# controller.net
KiCad netlist of a schematic drawn in EAGLE
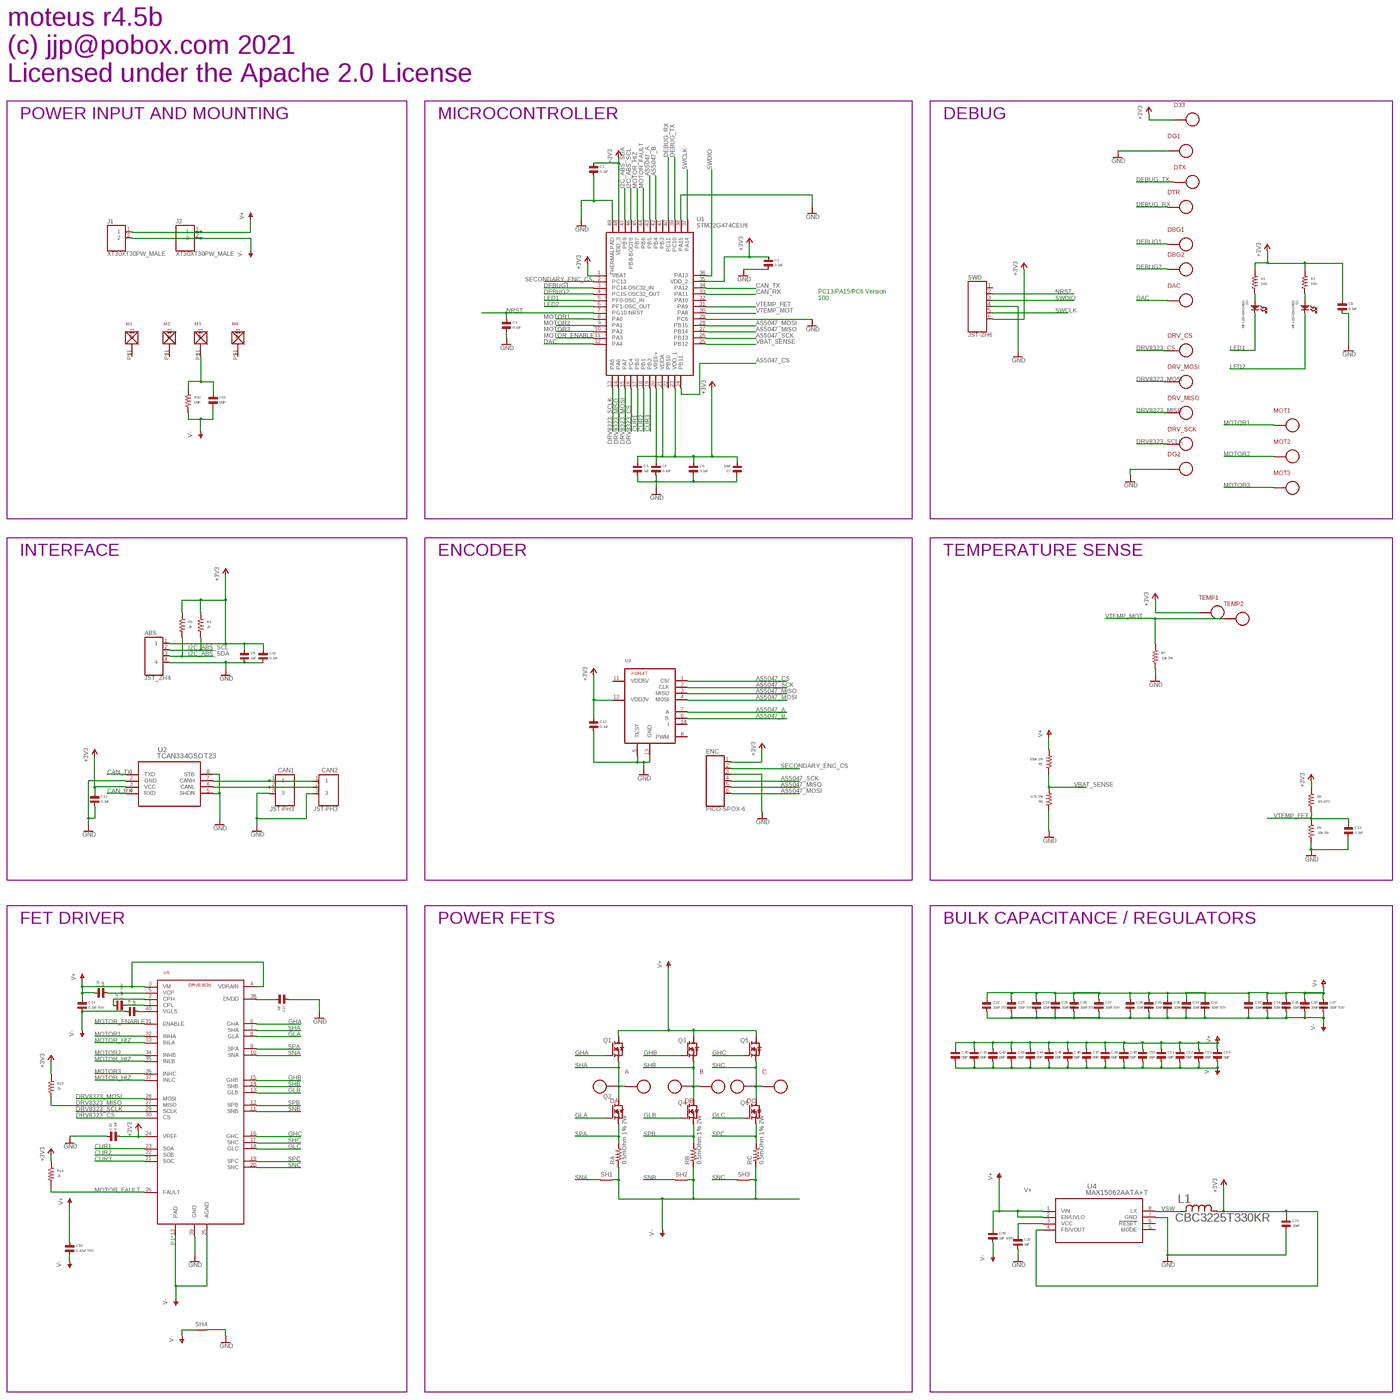
[diagram p0: schematic, sheet 1, overview]
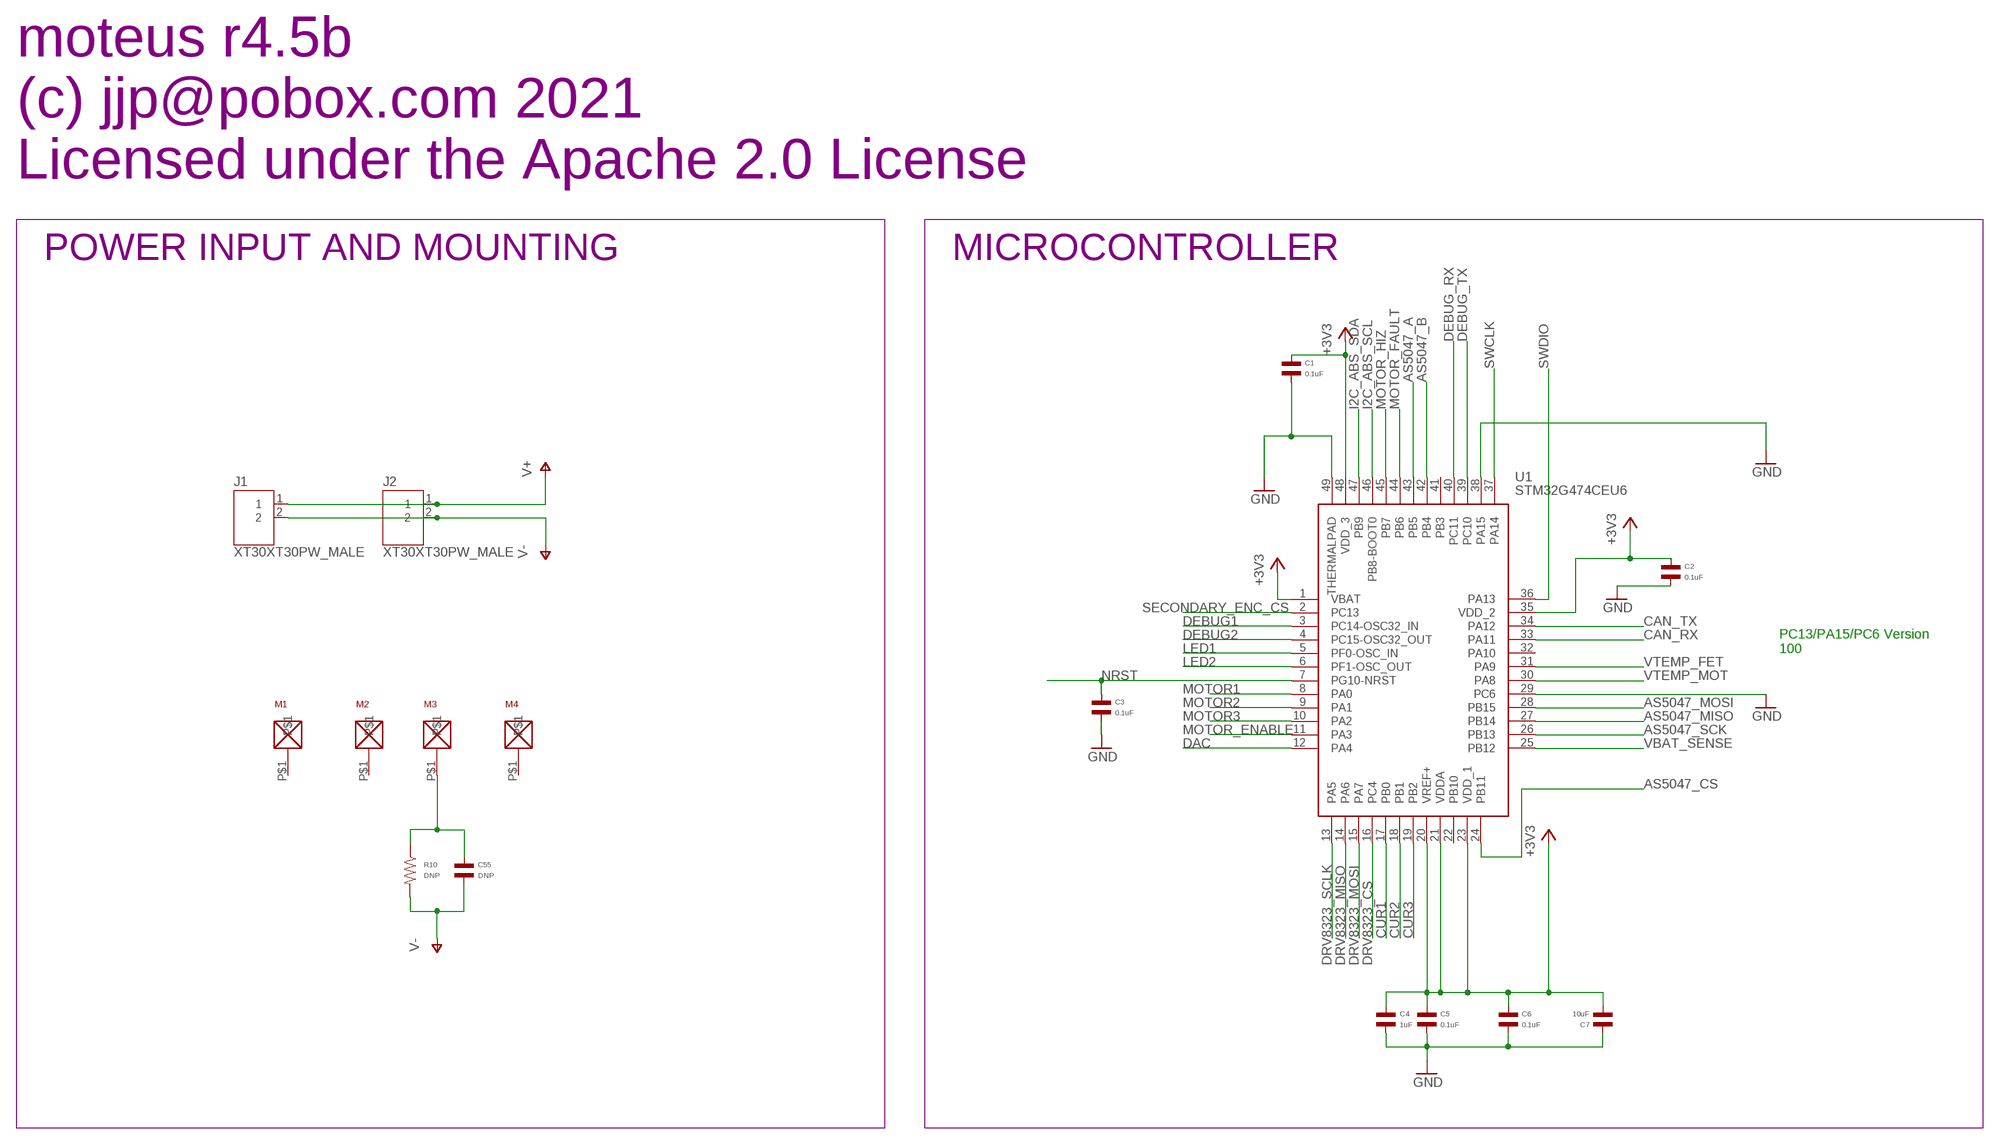
[diagram p1: schematic, sheet 1, part 1 of 4]
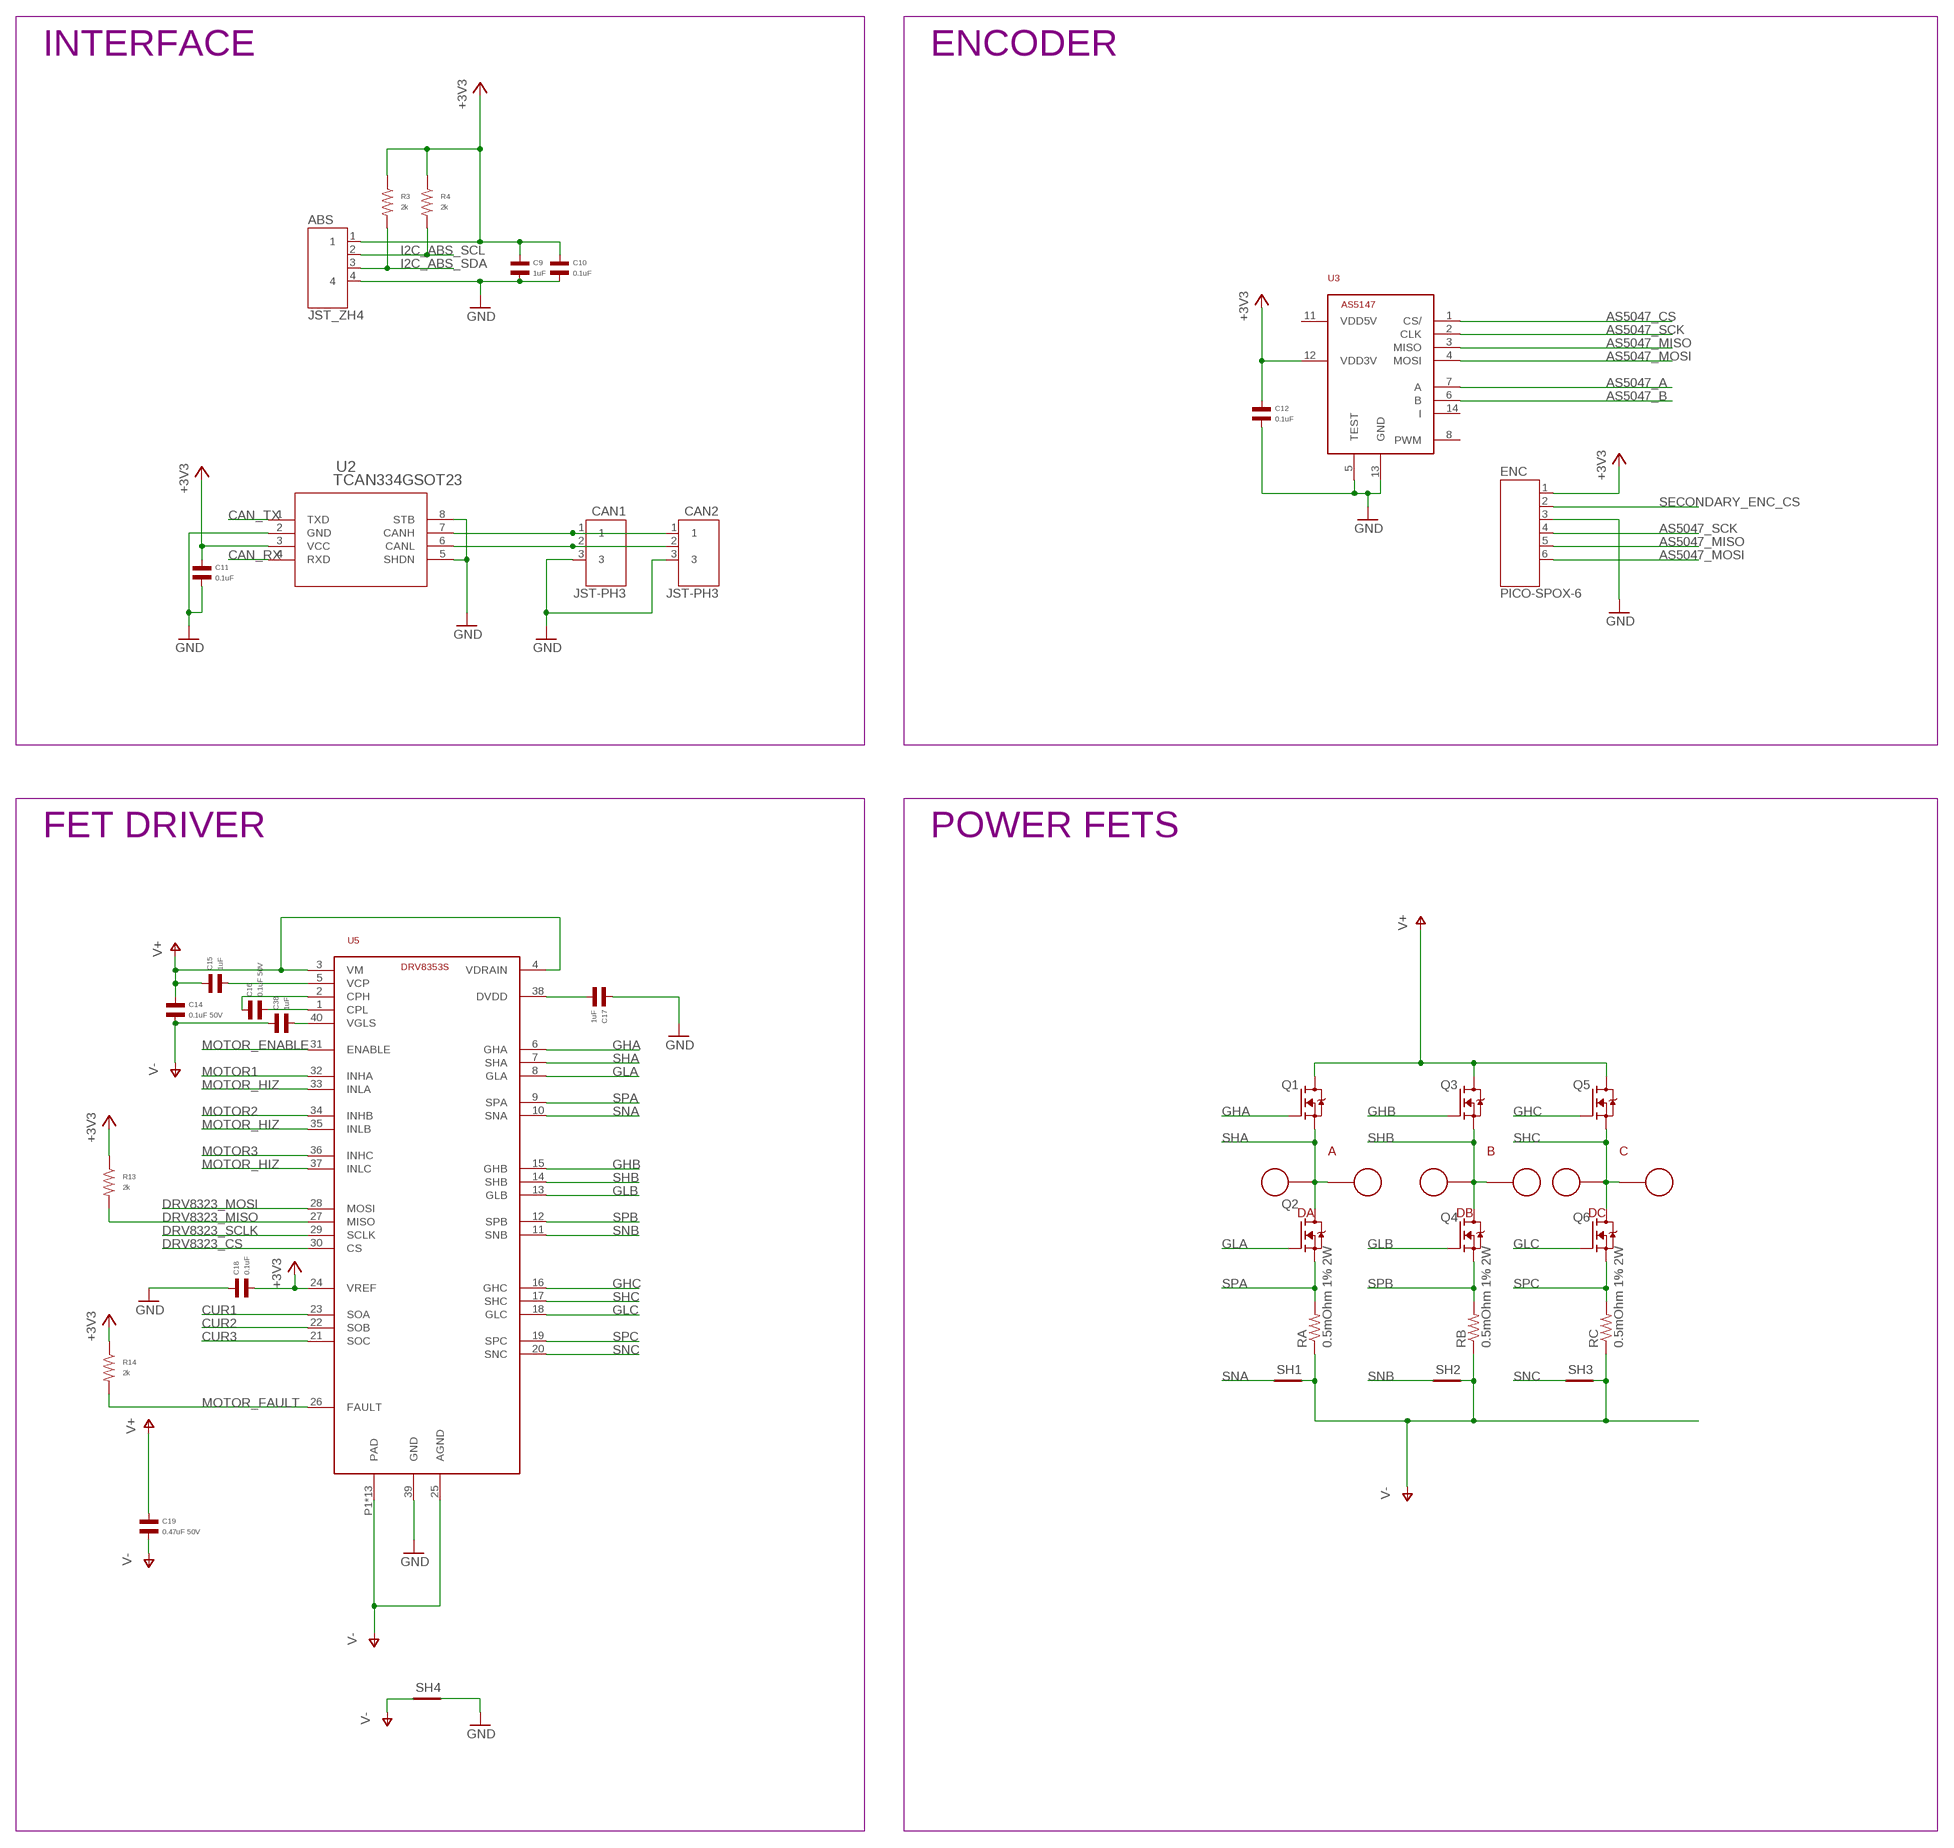
[diagram p2: schematic, sheet 1, part 2 of 4]
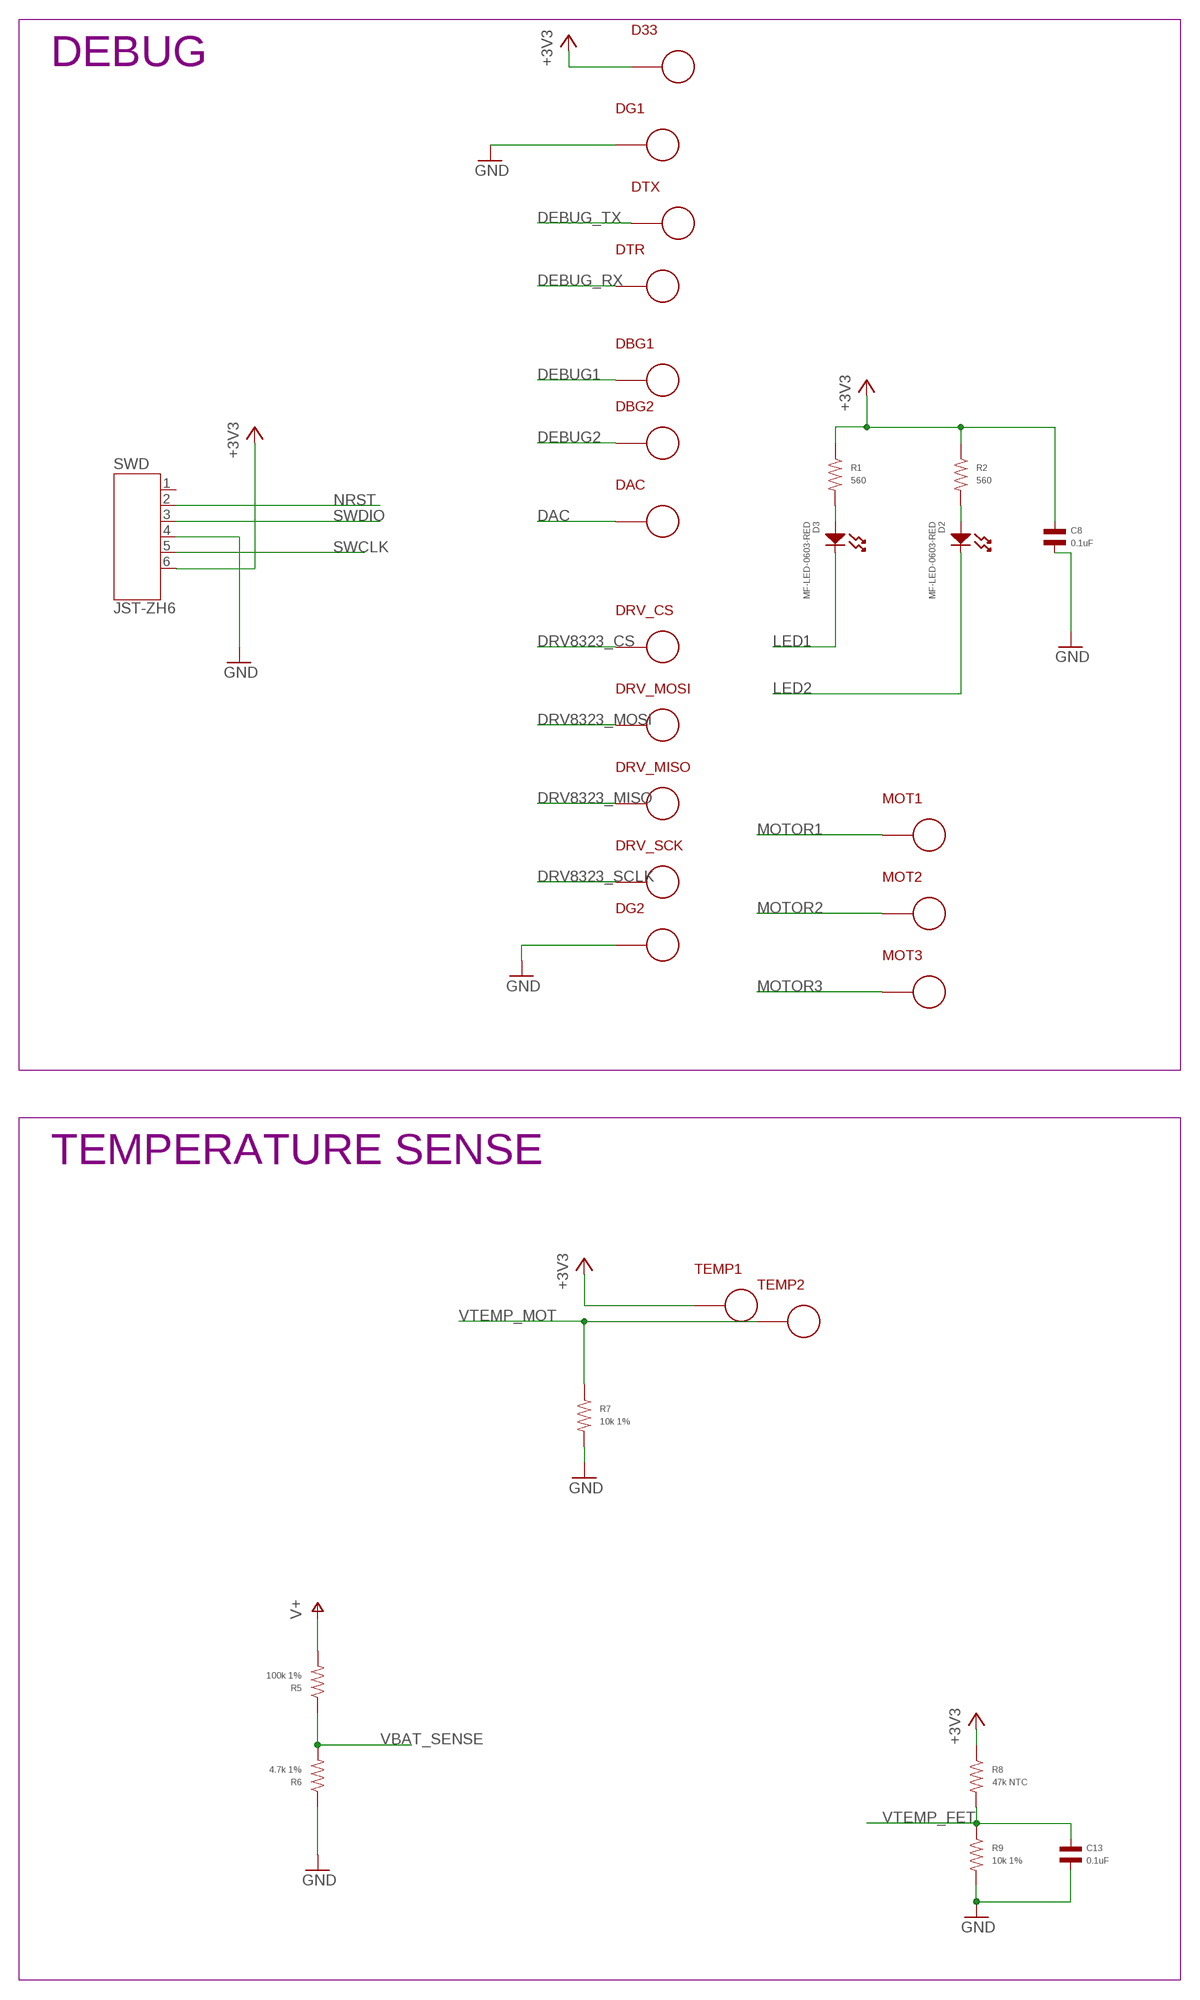
[diagram p3: schematic, sheet 1, part 3 of 4]
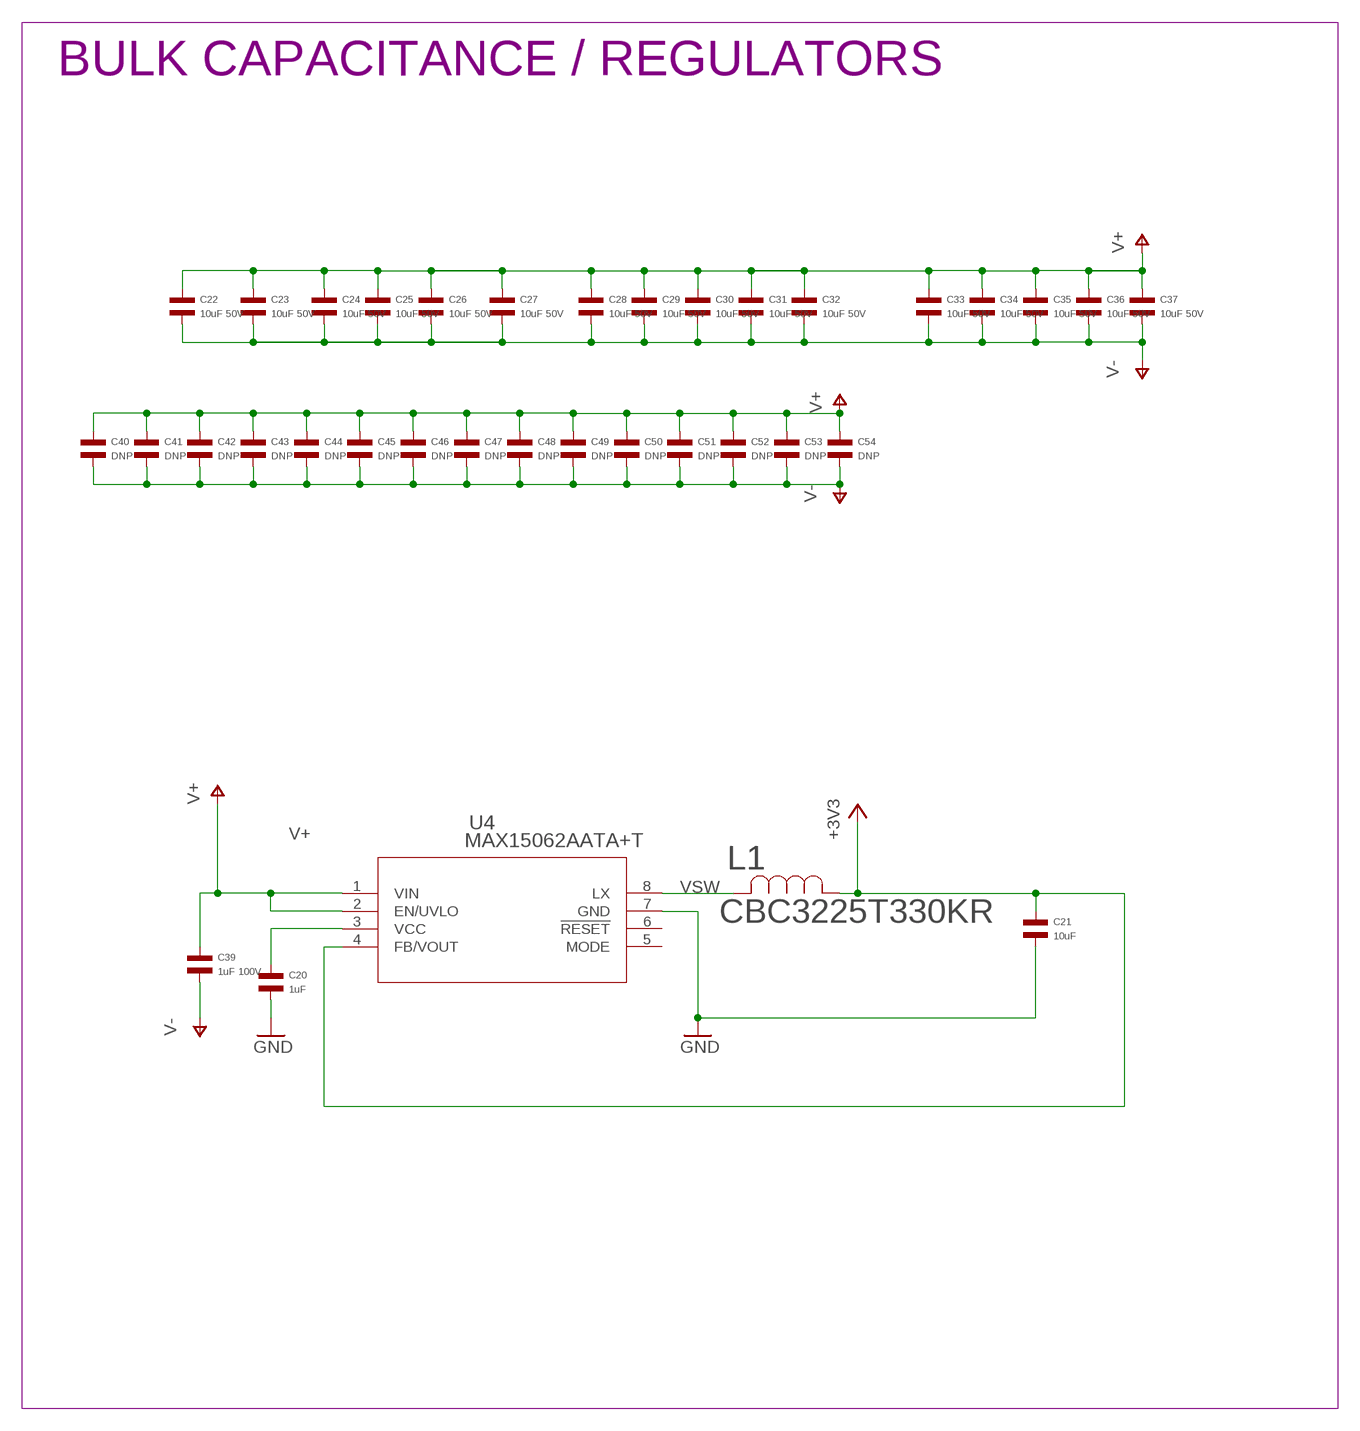
[diagram p4: schematic, sheet 1, part 4 of 4]

(export (version "E")
  (design (tool "Eeschema 10.0.6"))
  (components
    (comp (ref "A")
      (value "PAD16AWG_PAD")
      (footprint "eagle-import:16AWG_PAD")
      (libsource (lib "eagle-import") (part "PAD16AWG_PAD"))
    )
    (comp (ref "ABS")
      (value "JST_ZH4")
      (footprint "eagle-import:JST_S4B-ZR-SM4A-TF(LF)(SN)")
      (fields (field (name "MF") "JST") (field (name "MPN") "S4B-ZR-SM4A-TF(LF)(SN)"))
      (libsource (lib "eagle-import") (part "JST_ZH4"))
    )
    (comp (ref "B")
      (value "PAD16AWG_PAD")
      (footprint "eagle-import:16AWG_PAD")
      (libsource (lib "eagle-import") (part "PAD16AWG_PAD"))
    )
    (comp (ref "C")
      (value "PAD16AWG_PAD")
      (footprint "eagle-import:16AWG_PAD")
      (libsource (lib "eagle-import") (part "PAD16AWG_PAD"))
    )
    (comp (ref "C1")
      (value "0.1uF")
      (footprint "eagle-import:C0402")
      (fields (field (name "HOUSEPART") "YES") (field (name "MPN") "MF-CAP-0402-0.1uF"))
      (libsource (lib "eagle-import") (part "mfpassives_CAPACITOR_NP_0402"))
    )
    (comp (ref "C2")
      (value "0.1uF")
      (footprint "eagle-import:C0402")
      (fields (field (name "HOUSEPART") "YES") (field (name "MPN") "MF-CAP-0402-0.1uF"))
      (libsource (lib "eagle-import") (part "mfpassives_CAPACITOR_NP_0402"))
    )
    (comp (ref "C3")
      (value "0.1uF")
      (footprint "eagle-import:C0402")
      (fields (field (name "HOUSEPART") "YES") (field (name "MPN") "MF-CAP-0402-0.1uF"))
      (libsource (lib "eagle-import") (part "mfpassives_CAPACITOR_NP_0402"))
    )
    (comp (ref "C4")
      (value "1uF")
      (footprint "eagle-import:C0402")
      (fields (field (name "HOUSEPART") "YES") (field (name "MPN") "MF-CAP-0402-1uF"))
      (libsource (lib "eagle-import") (part "mfpassives_CAPACITOR_NP_0402"))
    )
    (comp (ref "C5")
      (value "0.1uF")
      (footprint "eagle-import:C0402")
      (fields (field (name "HOUSEPART") "YES") (field (name "MPN") "MF-CAP-0402-0.1uF"))
      (libsource (lib "eagle-import") (part "mfpassives_CAPACITOR_NP_0402"))
    )
    (comp (ref "C6")
      (value "0.1uF")
      (footprint "eagle-import:C0402")
      (fields (field (name "HOUSEPART") "YES") (field (name "MPN") "MF-CAP-0402-0.1uF"))
      (libsource (lib "eagle-import") (part "mfpassives_CAPACITOR_NP_0402"))
    )
    (comp (ref "C7")
      (value "10uF")
      (footprint "eagle-import:C1206")
      (fields (field (name "HOUSEPART") "YES") (field (name "MPN") "MF-CAP-1206-10uF"))
      (libsource (lib "eagle-import") (part "mfpassives_CAPACITOR_NP_1206"))
    )
    (comp (ref "C8")
      (value "0.1uF")
      (footprint "eagle-import:C0402")
      (fields (field (name "HOUSEPART") "YES") (field (name "MPN") "MF-CAP-0402-0.1uF"))
      (libsource (lib "eagle-import") (part "mfpassives_CAPACITOR_NP_0402"))
    )
    (comp (ref "C9")
      (value "1uF")
      (footprint "eagle-import:C0402")
      (fields (field (name "HOUSEPART") "YES") (field (name "MPN") "MF-CAP-0402-1uF"))
      (libsource (lib "eagle-import") (part "mfpassives_CAPACITOR_NP_0402"))
    )
    (comp (ref "C10")
      (value "0.1uF")
      (footprint "eagle-import:C0402")
      (fields (field (name "HOUSEPART") "YES") (field (name "MPN") "MF-CAP-0402-0.1uF"))
      (libsource (lib "eagle-import") (part "mfpassives_CAPACITOR_NP_0402"))
    )
    (comp (ref "C11")
      (value "0.1uF")
      (footprint "eagle-import:C0402")
      (fields (field (name "HOUSEPART") "YES") (field (name "MPN") "MF-CAP-0402-0.1uF"))
      (libsource (lib "eagle-import") (part "mfpassives_CAPACITOR_NP_0402"))
    )
    (comp (ref "C12")
      (value "0.1uF")
      (footprint "eagle-import:C0402")
      (fields (field (name "HOUSEPART") "YES") (field (name "MPN") "MF-CAP-0402-0.1uF"))
      (libsource (lib "eagle-import") (part "mfpassives_CAPACITOR_NP_0402"))
    )
    (comp (ref "C13")
      (value "0.1uF")
      (footprint "eagle-import:C0402")
      (fields (field (name "HOUSEPART") "YES") (field (name "MPN") "MF-CAP-0402-0.1uF"))
      (libsource (lib "eagle-import") (part "mfpassives_CAPACITOR_NP_0402"))
    )
    (comp (ref "C14")
      (value "0.1uF 50V")
      (footprint "eagle-import:C0402")
      (fields (field (name "MF") "TDK") (field (name "MPN") "CGA2B3X7R1H104K050BB"))
      (libsource (lib "eagle-import") (part "mfpassives_CAPACITOR_NP_0402"))
    )
    (comp (ref "C15")
      (value "1uF")
      (footprint "eagle-import:C0402")
      (fields (field (name "HOUSEPART") "YES") (field (name "MPN") "MF-CAP-0402-1uF"))
      (libsource (lib "eagle-import") (part "mfpassives_CAPACITOR_NP_0402"))
    )
    (comp (ref "C16")
      (value "0.1uF 50V")
      (footprint "eagle-import:C0402")
      (fields (field (name "MF") "TDK") (field (name "MPN") "CGA2B3X7R1H104K050BB"))
      (libsource (lib "eagle-import") (part "mfpassives_CAPACITOR_NP_0402"))
    )
    (comp (ref "C17")
      (value "1uF")
      (footprint "eagle-import:C0402")
      (fields (field (name "HOUSEPART") "YES") (field (name "MPN") "MF-CAP-0402-1uF"))
      (libsource (lib "eagle-import") (part "mfpassives_CAPACITOR_NP_0402"))
    )
    (comp (ref "C18")
      (value "0.1uF")
      (footprint "eagle-import:C0402")
      (fields (field (name "HOUSEPART") "YES") (field (name "MPN") "MF-CAP-0402-0.1uF"))
      (libsource (lib "eagle-import") (part "mfpassives_CAPACITOR_NP_0402"))
    )
    (comp (ref "C19")
      (value "0.47uF 50V")
      (footprint "eagle-import:C0402")
      (fields (field (name "MF") "Murata") (field (name "MPN") "GRM155R61H474KE11D"))
      (libsource (lib "eagle-import") (part "mfpassives_CAPACITOR_NP_0402"))
    )
    (comp (ref "C20")
      (value "1uF")
      (footprint "eagle-import:C0603")
      (fields (field (name "HOUSEPART") "1") (field (name "MPN") "MF-CAP-0603-1uF"))
      (libsource (lib "eagle-import") (part "mfpassives_CAPACITOR_NP_0603"))
    )
    (comp (ref "C21")
      (value "10uF")
      (footprint "eagle-import:C1206")
      (fields (field (name "HOUSEPART") "1") (field (name "MPN") "MF-CAP-1206-10uF"))
      (libsource (lib "eagle-import") (part "mfpassives_CAPACITOR_NP_1206"))
    )
    (comp (ref "C22")
      (value "10uF 50V")
      (footprint "eagle-import:C1206")
      (fields (field (name "MF") "TDK") (field (name "MPN") "C3216X7R1H106K160AE"))
      (libsource (lib "eagle-import") (part "mfpassives_CAPACITOR_NP_1206"))
    )
    (comp (ref "C23")
      (value "10uF 50V")
      (footprint "eagle-import:C1206")
      (fields (field (name "MF") "TDK") (field (name "MPN") "C3216X7R1H106K160AE"))
      (libsource (lib "eagle-import") (part "mfpassives_CAPACITOR_NP_1206"))
    )
    (comp (ref "C24")
      (value "10uF 50V")
      (footprint "eagle-import:C1206")
      (fields (field (name "MF") "TDK") (field (name "MPN") "C3216X7R1H106K160AE"))
      (libsource (lib "eagle-import") (part "mfpassives_CAPACITOR_NP_1206"))
    )
    (comp (ref "C25")
      (value "10uF 50V")
      (footprint "eagle-import:C1206")
      (fields (field (name "MF") "TDK") (field (name "MPN") "C3216X7R1H106K160AE"))
      (libsource (lib "eagle-import") (part "mfpassives_CAPACITOR_NP_1206"))
    )
    (comp (ref "C26")
      (value "10uF 50V")
      (footprint "eagle-import:C1206")
      (fields (field (name "MF") "TDK") (field (name "MPN") "C3216X7R1H106K160AE"))
      (libsource (lib "eagle-import") (part "mfpassives_CAPACITOR_NP_1206"))
    )
    (comp (ref "C27")
      (value "10uF 50V")
      (footprint "eagle-import:C1206")
      (fields (field (name "MF") "TDK") (field (name "MPN") "C3216X7R1H106K160AE"))
      (libsource (lib "eagle-import") (part "mfpassives_CAPACITOR_NP_1206"))
    )
    (comp (ref "C28")
      (value "10uF 50V")
      (footprint "eagle-import:C1206")
      (fields (field (name "MF") "TDK") (field (name "MPN") "C3216X7R1H106K160AE"))
      (libsource (lib "eagle-import") (part "mfpassives_CAPACITOR_NP_1206"))
    )
    (comp (ref "C29")
      (value "10uF 50V")
      (footprint "eagle-import:C1206")
      (fields (field (name "MF") "TDK") (field (name "MPN") "C3216X7R1H106K160AE"))
      (libsource (lib "eagle-import") (part "mfpassives_CAPACITOR_NP_1206"))
    )
    (comp (ref "C30")
      (value "10uF 50V")
      (footprint "eagle-import:C1206")
      (fields (field (name "MF") "TDK") (field (name "MPN") "C3216X7R1H106K160AE"))
      (libsource (lib "eagle-import") (part "mfpassives_CAPACITOR_NP_1206"))
    )
    (comp (ref "C31")
      (value "10uF 50V")
      (footprint "eagle-import:C1206")
      (fields (field (name "MF") "TDK") (field (name "MPN") "C3216X7R1H106K160AE"))
      (libsource (lib "eagle-import") (part "mfpassives_CAPACITOR_NP_1206"))
    )
    (comp (ref "C32")
      (value "10uF 50V")
      (footprint "eagle-import:C1206")
      (fields (field (name "MF") "TDK") (field (name "MPN") "C3216X7R1H106K160AE"))
      (libsource (lib "eagle-import") (part "mfpassives_CAPACITOR_NP_1206"))
    )
    (comp (ref "C33")
      (value "10uF 50V")
      (footprint "eagle-import:C1206")
      (fields (field (name "MF") "TDK") (field (name "MPN") "C3216X7R1H106K160AE"))
      (libsource (lib "eagle-import") (part "mfpassives_CAPACITOR_NP_1206"))
    )
    (comp (ref "C34")
      (value "10uF 50V")
      (footprint "eagle-import:C1206")
      (fields (field (name "MF") "TDK") (field (name "MPN") "C3216X7R1H106K160AE"))
      (libsource (lib "eagle-import") (part "mfpassives_CAPACITOR_NP_1206"))
    )
    (comp (ref "C35")
      (value "10uF 50V")
      (footprint "eagle-import:C1206")
      (fields (field (name "MF") "TDK") (field (name "MPN") "C3216X7R1H106K160AE"))
      (libsource (lib "eagle-import") (part "mfpassives_CAPACITOR_NP_1206"))
    )
    (comp (ref "C36")
      (value "10uF 50V")
      (footprint "eagle-import:C1206")
      (fields (field (name "MF") "TDK") (field (name "MPN") "C3216X7R1H106K160AE"))
      (libsource (lib "eagle-import") (part "mfpassives_CAPACITOR_NP_1206"))
    )
    (comp (ref "C37")
      (value "10uF 50V")
      (footprint "eagle-import:C1206")
      (fields (field (name "MF") "TDK") (field (name "MPN") "C3216X7R1H106K160AE"))
      (libsource (lib "eagle-import") (part "mfpassives_CAPACITOR_NP_1206"))
    )
    (comp (ref "C38")
      (value "1uF")
      (footprint "eagle-import:C0402")
      (fields (field (name "HOUSEPART") "YES") (field (name "MPN") "MF-CAP-0402-1uF"))
      (libsource (lib "eagle-import") (part "mfpassives_CAPACITOR_NP_0402"))
    )
    (comp (ref "C39")
      (value "1uF 100V")
      (footprint "eagle-import:C0805")
      (fields (field (name "MF") "MURATA") (field (name "MPN") "GCM21BC72A105KE36L"))
      (libsource (lib "eagle-import") (part "mfpassives_CAPACITOR_NP_0805"))
    )
    (comp (ref "C40")
      (value "DNP")
      (footprint "eagle-import:C1206_NOCREAM")
      (libsource (lib "eagle-import") (part "CAPACITOR_NP_1206_NOCREAM"))
    )
    (comp (ref "C41")
      (value "DNP")
      (footprint "eagle-import:C1206_NOCREAM")
      (libsource (lib "eagle-import") (part "CAPACITOR_NP_1206_NOCREAM"))
    )
    (comp (ref "C42")
      (value "DNP")
      (footprint "eagle-import:C1206_NOCREAM")
      (libsource (lib "eagle-import") (part "CAPACITOR_NP_1206_NOCREAM"))
    )
    (comp (ref "C43")
      (value "DNP")
      (footprint "eagle-import:C1206_NOCREAM")
      (libsource (lib "eagle-import") (part "CAPACITOR_NP_1206_NOCREAM"))
    )
    (comp (ref "C44")
      (value "DNP")
      (footprint "eagle-import:C1206_NOCREAM")
      (libsource (lib "eagle-import") (part "CAPACITOR_NP_1206_NOCREAM"))
    )
    (comp (ref "C45")
      (value "DNP")
      (footprint "eagle-import:C1206_NOCREAM")
      (libsource (lib "eagle-import") (part "CAPACITOR_NP_1206_NOCREAM"))
    )
    (comp (ref "C46")
      (value "DNP")
      (footprint "eagle-import:C1206_NOCREAM")
      (libsource (lib "eagle-import") (part "CAPACITOR_NP_1206_NOCREAM"))
    )
    (comp (ref "C47")
      (value "DNP")
      (footprint "eagle-import:C1206_NOCREAM")
      (libsource (lib "eagle-import") (part "CAPACITOR_NP_1206_NOCREAM"))
    )
    (comp (ref "C48")
      (value "DNP")
      (footprint "eagle-import:C1206_NOCREAM")
      (libsource (lib "eagle-import") (part "CAPACITOR_NP_1206_NOCREAM"))
    )
    (comp (ref "C49")
      (value "DNP")
      (footprint "eagle-import:C1206_NOCREAM")
      (libsource (lib "eagle-import") (part "CAPACITOR_NP_1206_NOCREAM"))
    )
    (comp (ref "C50")
      (value "DNP")
      (footprint "eagle-import:C1206_NOCREAM")
      (libsource (lib "eagle-import") (part "CAPACITOR_NP_1206_NOCREAM"))
    )
    (comp (ref "C51")
      (value "DNP")
      (footprint "eagle-import:C1206_NOCREAM")
      (libsource (lib "eagle-import") (part "CAPACITOR_NP_1206_NOCREAM"))
    )
    (comp (ref "C52")
      (value "DNP")
      (footprint "eagle-import:C1206_NOCREAM")
      (libsource (lib "eagle-import") (part "CAPACITOR_NP_1206_NOCREAM"))
    )
    (comp (ref "C53")
      (value "DNP")
      (footprint "eagle-import:C1206_NOCREAM")
      (libsource (lib "eagle-import") (part "CAPACITOR_NP_1206_NOCREAM"))
    )
    (comp (ref "C54")
      (value "DNP")
      (footprint "eagle-import:C1206_NOCREAM")
      (libsource (lib "eagle-import") (part "CAPACITOR_NP_1206_NOCREAM"))
    )
    (comp (ref "C55")
      (value "DNP")
      (footprint "eagle-import:C0402")
      (fields (field (name "POPULATE") "0"))
      (libsource (lib "eagle-import") (part "mfpassives_CAPACITOR_NP_0402"))
    )
    (comp (ref "CAN1")
      (value "JST-PH3")
      (footprint "eagle-import:JST_S3B-PH-SM4-TB(LF)(SN)")
      (fields (field (name "MF") "JST") (field (name "MPN") "S3B-PH-SM4-TB(LF)(SN)"))
      (libsource (lib "eagle-import") (part "JST-PH3"))
    )
    (comp (ref "CAN2")
      (value "JST-PH3")
      (footprint "eagle-import:JST_S3B-PH-SM4-TB(LF)(SN)")
      (fields (field (name "MF") "JST") (field (name "MPN") "S3B-PH-SM4-TB(LF)(SN)"))
      (libsource (lib "eagle-import") (part "JST-PH3"))
    )
    (comp (ref "D2")
      (value "MF-LED-0603-RED")
      (footprint "eagle-import:LED0603")
      (fields (field (name "HOUSEPART") "YES") (field (name "MPN") "MF-LED-0603-GREEN"))
      (libsource (lib "eagle-import") (part "LED_SINGLE-0603-RED"))
    )
    (comp (ref "D3")
      (value "MF-LED-0603-RED")
      (footprint "eagle-import:LED0603")
      (fields (field (name "HOUSEPART") "YES"))
      (libsource (lib "eagle-import") (part "LED_SINGLE-0603-RED"))
    )
    (comp (ref "D33")
      (value "PAD24AWG_PAD")
      (footprint "eagle-import:24AWG_PAD")
      (libsource (lib "eagle-import") (part "PAD24AWG_PAD"))
    )
    (comp (ref "DA")
      (value "PAD24AWG_PAD")
      (footprint "eagle-import:24AWG_PAD")
      (libsource (lib "eagle-import") (part "PAD24AWG_PAD"))
    )
    (comp (ref "DAC")
      (value "PAD24AWG_PAD")
      (footprint "eagle-import:24AWG_PAD")
      (libsource (lib "eagle-import") (part "PAD24AWG_PAD"))
    )
    (comp (ref "DB")
      (value "PAD24AWG_PAD")
      (footprint "eagle-import:24AWG_PAD")
      (libsource (lib "eagle-import") (part "PAD24AWG_PAD"))
    )
    (comp (ref "DBG1")
      (value "PAD24AWG_PAD")
      (footprint "eagle-import:24AWG_PAD")
      (libsource (lib "eagle-import") (part "PAD24AWG_PAD"))
    )
    (comp (ref "DBG2")
      (value "PAD24AWG_PAD")
      (footprint "eagle-import:24AWG_PAD")
      (libsource (lib "eagle-import") (part "PAD24AWG_PAD"))
    )
    (comp (ref "DC")
      (value "PAD24AWG_PAD")
      (footprint "eagle-import:24AWG_PAD")
      (libsource (lib "eagle-import") (part "PAD24AWG_PAD"))
    )
    (comp (ref "DG1")
      (value "PAD24AWG_PAD")
      (footprint "eagle-import:24AWG_PAD")
      (libsource (lib "eagle-import") (part "PAD24AWG_PAD"))
    )
    (comp (ref "DG2")
      (value "PAD24AWG_PAD")
      (footprint "eagle-import:24AWG_PAD")
      (libsource (lib "eagle-import") (part "PAD24AWG_PAD"))
    )
    (comp (ref "DRV_CS")
      (value "PAD24AWG_PAD")
      (footprint "eagle-import:24AWG_PAD")
      (libsource (lib "eagle-import") (part "PAD24AWG_PAD"))
    )
    (comp (ref "DRV_MISO")
      (value "PAD24AWG_PAD")
      (footprint "eagle-import:24AWG_PAD")
      (libsource (lib "eagle-import") (part "PAD24AWG_PAD"))
    )
    (comp (ref "DRV_MOSI")
      (value "PAD24AWG_PAD")
      (footprint "eagle-import:24AWG_PAD")
      (libsource (lib "eagle-import") (part "PAD24AWG_PAD"))
    )
    (comp (ref "DRV_SCK")
      (value "PAD24AWG_PAD")
      (footprint "eagle-import:24AWG_PAD")
      (libsource (lib "eagle-import") (part "PAD24AWG_PAD"))
    )
    (comp (ref "DTR")
      (value "PAD24AWG_PAD")
      (footprint "eagle-import:24AWG_PAD")
      (libsource (lib "eagle-import") (part "PAD24AWG_PAD"))
    )
    (comp (ref "DTX")
      (value "PAD24AWG_PAD")
      (footprint "eagle-import:24AWG_PAD")
      (libsource (lib "eagle-import") (part "PAD24AWG_PAD"))
    )
    (comp (ref "ENC")
      (value "PICO-SPOX-6")
      (footprint "eagle-import:PICO-SPOX-SMT-RA-6")
      (libsource (lib "eagle-import") (part "PICO-SPOX-6"))
    )
    (comp (ref "J1")
      (value "XT30XT30PW_MALE")
      (footprint "eagle-import:XT30PW_MALE")
      (libsource (lib "eagle-import") (part "XT30XT30PW_MALE"))
    )
    (comp (ref "J2")
      (value "XT30XT30PW_MALE")
      (footprint "eagle-import:XT30PW_MALE")
      (libsource (lib "eagle-import") (part "XT30XT30PW_MALE"))
    )
    (comp (ref "L1")
      (value "CBC3225T330KR")
      (footprint "eagle-import:IND_TAIYO_CBC3225_TAY")
      (libsource (lib "eagle-import") (part "CBC3225T330KR"))
    )
    (comp (ref "M1")
      (value "MOUNT")
      (footprint "eagle-import:M2.5MOUNT")
      (libsource (lib "eagle-import") (part "MOUNT"))
    )
    (comp (ref "M2")
      (value "MOUNT")
      (footprint "eagle-import:M2.5MOUNT")
      (libsource (lib "eagle-import") (part "MOUNT"))
    )
    (comp (ref "M3")
      (value "MOUNT")
      (footprint "eagle-import:M2.5MOUNT")
      (libsource (lib "eagle-import") (part "MOUNT"))
    )
    (comp (ref "M4")
      (value "MOUNT")
      (footprint "eagle-import:M2.5MOUNT")
      (libsource (lib "eagle-import") (part "MOUNT"))
    )
    (comp (ref "MOT1")
      (value "PAD24AWG_PAD")
      (footprint "eagle-import:24AWG_PAD")
      (libsource (lib "eagle-import") (part "PAD24AWG_PAD"))
    )
    (comp (ref "MOT2")
      (value "PAD24AWG_PAD")
      (footprint "eagle-import:24AWG_PAD")
      (libsource (lib "eagle-import") (part "PAD24AWG_PAD"))
    )
    (comp (ref "MOT3")
      (value "PAD24AWG_PAD")
      (footprint "eagle-import:24AWG_PAD")
      (libsource (lib "eagle-import") (part "PAD24AWG_PAD"))
    )
    (comp (ref "Q1")
      (value "TPH1R204PLSOP_ADVANCE_8")
      (footprint "eagle-import:SOP_ADVANCE_8")
      (fields
        (field (name "MF") "Toshiba")
        (field (name "MPN") "TPH1R204PL")
        (field (name "MF_1") "Toshiba")
        (field (name "MPN_1") "TPH2R506PL,L1Q")
      )
      (libsource (lib "eagle-import") (part "TPH1R204PLSOP_ADVANCE_8"))
    )
    (comp (ref "Q2")
      (value "TPH1R204PLSOP_ADVANCE_8")
      (footprint "eagle-import:SOP_ADVANCE_8")
      (fields
        (field (name "MF") "Toshiba")
        (field (name "MPN") "TPH1R204PL")
        (field (name "MF_1") "Toshiba")
        (field (name "MPN_1") "TPH2R506PL,L1Q")
      )
      (libsource (lib "eagle-import") (part "TPH1R204PLSOP_ADVANCE_8"))
    )
    (comp (ref "Q3")
      (value "TPH1R204PLSOP_ADVANCE_8")
      (footprint "eagle-import:SOP_ADVANCE_8")
      (fields
        (field (name "MF") "Toshiba")
        (field (name "MPN") "TPH1R204PL")
        (field (name "MF_1") "Toshiba")
        (field (name "MPN_1") "TPH2R506PL,L1Q")
      )
      (libsource (lib "eagle-import") (part "TPH1R204PLSOP_ADVANCE_8"))
    )
    (comp (ref "Q4")
      (value "TPH1R204PLSOP_ADVANCE_8")
      (footprint "eagle-import:SOP_ADVANCE_8")
      (fields
        (field (name "MF") "Toshiba")
        (field (name "MPN") "TPH1R204PL")
        (field (name "MF_1") "Toshiba")
        (field (name "MPN_1") "TPH2R506PL,L1Q")
      )
      (libsource (lib "eagle-import") (part "TPH1R204PLSOP_ADVANCE_8"))
    )
    (comp (ref "Q5")
      (value "TPH1R204PLSOP_ADVANCE_8")
      (footprint "eagle-import:SOP_ADVANCE_8")
      (fields
        (field (name "MF") "Toshiba")
        (field (name "MPN") "TPH1R204PL")
        (field (name "MF_1") "Toshiba")
        (field (name "MPN_1") "TPH2R506PL,L1Q")
      )
      (libsource (lib "eagle-import") (part "TPH1R204PLSOP_ADVANCE_8"))
    )
    (comp (ref "Q6")
      (value "TPH1R204PLSOP_ADVANCE_8")
      (footprint "eagle-import:SOP_ADVANCE_8")
      (fields
        (field (name "MF") "Toshiba")
        (field (name "MPN") "TPH1R204PL")
        (field (name "MF_1") "Toshiba")
        (field (name "MPN_1") "TPH2R506PL,L1Q")
      )
      (libsource (lib "eagle-import") (part "TPH1R204PLSOP_ADVANCE_8"))
    )
    (comp (ref "R1")
      (value "560")
      (footprint "eagle-import:R0402")
      (fields (field (name "HOUSEPART") "1") (field (name "MPN") "MF-RES-0402-560"))
      (libsource (lib "eagle-import") (part "RESISTOR_0402"))
    )
    (comp (ref "R2")
      (value "560")
      (footprint "eagle-import:R0402")
      (fields (field (name "HOUSEPART") "1") (field (name "MPN") "MF-RES-0402-560"))
      (libsource (lib "eagle-import") (part "RESISTOR_0402"))
    )
    (comp (ref "R3")
      (value "2k")
      (footprint "eagle-import:R0402")
      (fields (field (name "HOUSEPART") "YES") (field (name "MPN") "MF-RES-0402-2K"))
      (libsource (lib "eagle-import") (part "RESISTOR_0402"))
    )
    (comp (ref "R4")
      (value "2k")
      (footprint "eagle-import:R0402")
      (fields (field (name "HOUSEPART") "YES") (field (name "MPN") "MF-RES-0402-2K"))
      (libsource (lib "eagle-import") (part "RESISTOR_0402"))
    )
    (comp (ref "R5")
      (value "100k 1%")
      (footprint "eagle-import:R0402")
      (fields (field (name "MF") "Yageo") (field (name "MPN") "RC0402FR-07100KL"))
      (libsource (lib "eagle-import") (part "RESISTOR_0402"))
    )
    (comp (ref "R6")
      (value "4.7k 1%")
      (footprint "eagle-import:R0402")
      (fields (field (name "MF") "Yageo") (field (name "MPN") "RC0402FR-074K7L"))
      (libsource (lib "eagle-import") (part "RESISTOR_0402"))
    )
    (comp (ref "R7")
      (value "10k 1%")
      (footprint "eagle-import:R0402")
      (fields (field (name "MF") "Yageo") (field (name "MPN") "RC0402FR-0710KL"))
      (libsource (lib "eagle-import") (part "RESISTOR_0402"))
    )
    (comp (ref "R8")
      (value "47k NTC")
      (footprint "eagle-import:R0402")
      (fields (field (name "MF") "Murata") (field (name "MPN") "NCP15WB473F03RC"))
      (libsource (lib "eagle-import") (part "RESISTOR_0402"))
    )
    (comp (ref "R9")
      (value "10k 1%")
      (footprint "eagle-import:R0402")
      (fields (field (name "MF") "Yageo") (field (name "MPN") "RC0402FR-0710KL"))
      (libsource (lib "eagle-import") (part "RESISTOR_0402"))
    )
    (comp (ref "R10")
      (value "DNP")
      (footprint "eagle-import:R0402")
      (fields (field (name "POPULATE") "0"))
      (libsource (lib "eagle-import") (part "RESISTOR_0402"))
    )
    (comp (ref "R13")
      (value "2k")
      (footprint "eagle-import:R0402")
      (fields (field (name "HOUSEPART") "YES") (field (name "MPN") "MF-RES-0402-2K"))
      (libsource (lib "eagle-import") (part "RESISTOR_0402"))
    )
    (comp (ref "R14")
      (value "2k")
      (footprint "eagle-import:R0402")
      (fields (field (name "HOUSEPART") "YES") (field (name "MPN") "MF-RES-0402-2K"))
      (libsource (lib "eagle-import") (part "RESISTOR_0402"))
    )
    (comp (ref "RA")
      (value "0.5mOhm 1% 2W")
      (footprint "eagle-import:M1206")
      (fields (field (name "MF") "Stackpole Electronics") (field (name "MPN") "HCS1206FTL500"))
      (libsource (lib "eagle-import") (part "R-US_M1206"))
    )
    (comp (ref "RB")
      (value "0.5mOhm 1% 2W")
      (footprint "eagle-import:M1206")
      (fields (field (name "MF") "Stackpole Electronics") (field (name "MPN") "HCS1206FTL500"))
      (libsource (lib "eagle-import") (part "R-US_M1206"))
    )
    (comp (ref "RC")
      (value "0.5mOhm 1% 2W")
      (footprint "eagle-import:M1206")
      (fields (field (name "MF") "Stackpole Electronics") (field (name "MPN") "HCS1206FTL500"))
      (libsource (lib "eagle-import") (part "R-US_M1206"))
    )
    (comp (ref "SH1")
      (value "SHORTT5")
      (footprint "eagle-import:SHORT_TOP-50")
      (libsource (lib "eagle-import") (part "SHORTT5"))
    )
    (comp (ref "SH2")
      (value "SHORTT5")
      (footprint "eagle-import:SHORT_TOP-50")
      (libsource (lib "eagle-import") (part "SHORTT5"))
    )
    (comp (ref "SH3")
      (value "SHORTT5")
      (footprint "eagle-import:SHORT_TOP-50")
      (libsource (lib "eagle-import") (part "SHORTT5"))
    )
    (comp (ref "SH4")
      (value "SHORTBIG")
      (footprint "eagle-import:SHORT_TOP-BIG")
      (libsource (lib "eagle-import") (part "SHORTBIG"))
    )
    (comp (ref "SWD")
      (value "JST-ZH6")
      (footprint "eagle-import:JST_S6B-ZR-SM4A-TF(LF)(SN)")
      (fields (field (name "MF") "JST") (field (name "MPN") "S6B-ZR-SM4A-TF(LF)(SN)"))
      (libsource (lib "eagle-import") (part "JST-ZH6"))
    )
    (comp (ref "TEMP1")
      (value "PAD24AWG_PAD")
      (footprint "eagle-import:24AWG_PAD")
      (libsource (lib "eagle-import") (part "PAD24AWG_PAD"))
    )
    (comp (ref "TEMP2")
      (value "PAD24AWG_PAD")
      (footprint "eagle-import:24AWG_PAD")
      (libsource (lib "eagle-import") (part "PAD24AWG_PAD"))
    )
    (comp (ref "U1")
      (value "STM32G474CEU6")
      (footprint "eagle-import:QFN50P700X700X60-49N")
      (fields (field (name "MOUSER_PART_NUMBER") "511-STM32G474CEU6"))
      (libsource (lib "eagle-import") (part "STM32G474CEU6"))
    )
    (comp (ref "U2")
      (value "TCAN334GSOT23")
      (footprint "eagle-import:SOT23-8")
      (fields (field (name "MF") "TI") (field (name "MPN") "TCAN334GDCNT"))
      (libsource (lib "eagle-import") (part "TCAN334GSOT23"))
    )
    (comp (ref "U3")
      (value "AS5147")
      (footprint "eagle-import:TSSOP14")
      (fields (field (name "MF") "AMS") (field (name "MPN") "AS5047P-ATSM"))
      (libsource (lib "eagle-import") (part "AS5147"))
    )
    (comp (ref "U4")
      (value "MAX15062AATA+T")
      (footprint "eagle-import:21-0487A_MXM")
      (fields (field (name "COPYRIGHT") "Copyright (C) 2018 Accelerated Designs. All rights reserved"))
      (libsource (lib "eagle-import") (part "MAX15062AATA+T"))
    )
    (comp (ref "U5")
      (value "DRV8353S")
      (footprint "eagle-import:WQFN-40")
      (fields (field (name "MF") "TI") (field (name "MPN") "DRV8353FSRTAR"))
      (libsource (lib "eagle-import") (part "DRV8353S"))
    )
  )
  (nets
    (net (code "1") (name "+3V3") (class "Default")
      (node (ref "ABS") (pin "1") (pinfunction "1_1") (pintype "passive"))
      (node (ref "C1") (pin "P$1") (pinfunction "P$1_P$1") (pintype "passive"))
      (node (ref "C10") (pin "P$1") (pinfunction "P$1_P$1") (pintype "passive"))
      (node (ref "C11") (pin "P$1") (pinfunction "P$1_P$1") (pintype "passive"))
      (node (ref "C12") (pin "P$1") (pinfunction "P$1_P$1") (pintype "passive"))
      (node (ref "C18") (pin "P$2") (pinfunction "P$2_P$2") (pintype "passive"))
      (node (ref "C2") (pin "P$1") (pinfunction "P$1_P$1") (pintype "passive"))
      (node (ref "C21") (pin "P$1") (pinfunction "P$1_P$1") (pintype "passive"))
      (node (ref "C4") (pin "P$1") (pinfunction "P$1_P$1") (pintype "passive"))
      (node (ref "C5") (pin "P$1") (pinfunction "P$1_P$1") (pintype "passive"))
      (node (ref "C6") (pin "P$1") (pinfunction "P$1_P$1") (pintype "passive"))
      (node (ref "C7") (pin "P$2") (pinfunction "P$2_P$2") (pintype "passive"))
      (node (ref "C8") (pin "P$1") (pinfunction "P$1_P$1") (pintype "passive"))
      (node (ref "C9") (pin "P$1") (pinfunction "P$1_P$1") (pintype "passive"))
      (node (ref "D33") (pin "P$1") (pinfunction "P$1_P$1") (pintype "bidirectional"))
      (node (ref "ENC") (pin "1") (pinfunction "1_1") (pintype "passive"))
      (node (ref "L1") (pin "1") (pinfunction "1_1") (pintype "passive"))
      (node (ref "R1") (pin "P$1") (pinfunction "P$1_P$1") (pintype "passive"))
      (node (ref "R13") (pin "P$1") (pinfunction "P$1_P$1") (pintype "passive"))
      (node (ref "R14") (pin "P$1") (pinfunction "P$1_P$1") (pintype "passive"))
      (node (ref "R2") (pin "P$1") (pinfunction "P$1_P$1") (pintype "passive"))
      (node (ref "R3") (pin "P$1") (pinfunction "P$1_P$1") (pintype "passive"))
      (node (ref "R4") (pin "P$1") (pinfunction "P$1_P$1") (pintype "passive"))
      (node (ref "R8") (pin "P$1") (pinfunction "P$1_P$1") (pintype "passive"))
      (node (ref "SWD") (pin "6") (pinfunction "6_6") (pintype "passive"))
      (node (ref "TEMP1") (pin "P$1") (pinfunction "P$1_P$1") (pintype "bidirectional"))
      (node (ref "U1") (pin "1") (pinfunction "VBAT_1") (pintype "bidirectional"))
      (node (ref "U1") (pin "20") (pinfunction "VREF+_20") (pintype "bidirectional"))
      (node (ref "U1") (pin "21") (pinfunction "VDDA_21") (pintype "bidirectional"))
      (node (ref "U1") (pin "23") (pinfunction "VDD_1_23") (pintype "bidirectional"))
      (node (ref "U1") (pin "35") (pinfunction "VDD_2_35") (pintype "bidirectional"))
      (node (ref "U1") (pin "48") (pinfunction "VDD_3_48") (pintype "bidirectional"))
      (node (ref "U2") (pin "3") (pinfunction "VCC_3") (pintype "power_in"))
      (node (ref "U3") (pin "12") (pinfunction "VDD3V_12") (pintype "bidirectional"))
      (node (ref "U4") (pin "4") (pinfunction "FB/VOUT_4") (pintype "bidirectional"))
      (node (ref "U5") (pin "24") (pinfunction "VREF_24") (pintype "bidirectional"))
    )
    (net (code "2") (name "/AS5047_A") (class "Default")
      (node (ref "U1") (pin "43") (pinfunction "PB5_43") (pintype "bidirectional"))
      (node (ref "U3") (pin "7") (pinfunction "A_7") (pintype "bidirectional"))
    )
    (net (code "3") (name "/AS5047_B") (class "Default")
      (node (ref "U1") (pin "42") (pinfunction "PB4_42") (pintype "bidirectional"))
      (node (ref "U3") (pin "6") (pinfunction "B_6") (pintype "bidirectional"))
    )
    (net (code "4") (name "/AS5047_CS") (class "Default")
      (node (ref "U1") (pin "24") (pinfunction "PB11_24") (pintype "bidirectional"))
      (node (ref "U3") (pin "1") (pinfunction "CS/_1") (pintype "bidirectional"))
    )
    (net (code "5") (name "/AS5047_MISO") (class "Default")
      (node (ref "ENC") (pin "5") (pinfunction "5_5") (pintype "passive"))
      (node (ref "U1") (pin "27") (pinfunction "PB14_27") (pintype "bidirectional"))
      (node (ref "U3") (pin "3") (pinfunction "MISO_3") (pintype "bidirectional"))
    )
    (net (code "6") (name "/AS5047_MOSI") (class "Default")
      (node (ref "ENC") (pin "6") (pinfunction "6_6") (pintype "passive"))
      (node (ref "U1") (pin "28") (pinfunction "PB15_28") (pintype "bidirectional"))
      (node (ref "U3") (pin "4") (pinfunction "MOSI_4") (pintype "bidirectional"))
    )
    (net (code "7") (name "/AS5047_SCK") (class "Default")
      (node (ref "ENC") (pin "4") (pinfunction "4_4") (pintype "passive"))
      (node (ref "U1") (pin "26") (pinfunction "PB13_26") (pintype "bidirectional"))
      (node (ref "U3") (pin "2") (pinfunction "CLK_2") (pintype "bidirectional"))
    )
    (net (code "8") (name "/CAN_RX") (class "Default")
      (node (ref "U1") (pin "33") (pinfunction "PA11_33") (pintype "bidirectional"))
      (node (ref "U2") (pin "4") (pinfunction "RXD_4") (pintype "output"))
    )
    (net (code "9") (name "/CAN_TX") (class "Default")
      (node (ref "U1") (pin "34") (pinfunction "PA12_34") (pintype "bidirectional"))
      (node (ref "U2") (pin "1") (pinfunction "TXD_1") (pintype "input"))
    )
    (net (code "10") (name "/CUR1") (class "Default")
      (node (ref "U1") (pin "17") (pinfunction "PB0_17") (pintype "bidirectional"))
      (node (ref "U5") (pin "23") (pinfunction "SOA_23") (pintype "bidirectional"))
    )
    (net (code "11") (name "/CUR2") (class "Default")
      (node (ref "U1") (pin "18") (pinfunction "PB1_18") (pintype "bidirectional"))
      (node (ref "U5") (pin "22") (pinfunction "SOB_22") (pintype "bidirectional"))
    )
    (net (code "12") (name "/CUR3") (class "Default")
      (node (ref "U1") (pin "19") (pinfunction "PB2_19") (pintype "bidirectional"))
      (node (ref "U5") (pin "21") (pinfunction "SOC_21") (pintype "bidirectional"))
    )
    (net (code "13") (name "/DAC") (class "Default")
      (node (ref "DAC") (pin "P$1") (pinfunction "P$1_P$1") (pintype "bidirectional"))
      (node (ref "U1") (pin "12") (pinfunction "PA4_12") (pintype "bidirectional"))
    )
    (net (code "14") (name "/DEBUG1") (class "Default")
      (node (ref "DBG1") (pin "P$1") (pinfunction "P$1_P$1") (pintype "bidirectional"))
      (node (ref "U1") (pin "3") (pinfunction "PC14-OSC32_IN_3") (pintype "bidirectional"))
    )
    (net (code "15") (name "/DEBUG2") (class "Default")
      (node (ref "DBG2") (pin "P$1") (pinfunction "P$1_P$1") (pintype "bidirectional"))
      (node (ref "U1") (pin "4") (pinfunction "PC15-OSC32_OUT_4") (pintype "bidirectional"))
    )
    (net (code "16") (name "/DEBUG_RX") (class "Default")
      (node (ref "DTR") (pin "P$1") (pinfunction "P$1_P$1") (pintype "bidirectional"))
      (node (ref "U1") (pin "40") (pinfunction "PC11_40") (pintype "bidirectional"))
    )
    (net (code "17") (name "/DEBUG_TX") (class "Default")
      (node (ref "DTX") (pin "P$1") (pinfunction "P$1_P$1") (pintype "bidirectional"))
      (node (ref "U1") (pin "39") (pinfunction "PC10_39") (pintype "bidirectional"))
    )
    (net (code "18") (name "/DRV8323_CS") (class "Default")
      (node (ref "DRV_CS") (pin "P$1") (pinfunction "P$1_P$1") (pintype "bidirectional"))
      (node (ref "U1") (pin "16") (pinfunction "PC4_16") (pintype "bidirectional"))
      (node (ref "U5") (pin "30") (pinfunction "CS_30") (pintype "bidirectional"))
    )
    (net (code "19") (name "/DRV8323_MISO") (class "Default")
      (node (ref "DRV_MISO") (pin "P$1") (pinfunction "P$1_P$1") (pintype "bidirectional"))
      (node (ref "R13") (pin "P$2") (pinfunction "P$2_P$2") (pintype "passive"))
      (node (ref "U1") (pin "14") (pinfunction "PA6_14") (pintype "bidirectional"))
      (node (ref "U5") (pin "27") (pinfunction "MISO_27") (pintype "bidirectional"))
    )
    (net (code "20") (name "/DRV8323_MOSI") (class "Default")
      (node (ref "DRV_MOSI") (pin "P$1") (pinfunction "P$1_P$1") (pintype "bidirectional"))
      (node (ref "U1") (pin "15") (pinfunction "PA7_15") (pintype "bidirectional"))
      (node (ref "U5") (pin "28") (pinfunction "MOSI_28") (pintype "bidirectional"))
    )
    (net (code "21") (name "/DRV8323_SCLK") (class "Default")
      (node (ref "DRV_SCK") (pin "P$1") (pinfunction "P$1_P$1") (pintype "bidirectional"))
      (node (ref "U1") (pin "13") (pinfunction "PA5_13") (pintype "bidirectional"))
      (node (ref "U5") (pin "29") (pinfunction "SCLK_29") (pintype "bidirectional"))
    )
    (net (code "22") (name "/GHA") (class "Default")
      (node (ref "Q1") (pin "4") (pinfunction "G_4") (pintype "passive"))
      (node (ref "U5") (pin "6") (pinfunction "GHA_6") (pintype "bidirectional"))
    )
    (net (code "23") (name "/GHB") (class "Default")
      (node (ref "Q3") (pin "4") (pinfunction "G_4") (pintype "passive"))
      (node (ref "U5") (pin "15") (pinfunction "GHB_15") (pintype "bidirectional"))
    )
    (net (code "24") (name "/GHC") (class "Default")
      (node (ref "Q5") (pin "4") (pinfunction "G_4") (pintype "passive"))
      (node (ref "U5") (pin "16") (pinfunction "GHC_16") (pintype "bidirectional"))
    )
    (net (code "25") (name "/GLA") (class "Default")
      (node (ref "Q2") (pin "4") (pinfunction "G_4") (pintype "passive"))
      (node (ref "U5") (pin "8") (pinfunction "GLA_8") (pintype "bidirectional"))
    )
    (net (code "26") (name "/GLB") (class "Default")
      (node (ref "Q4") (pin "4") (pinfunction "G_4") (pintype "passive"))
      (node (ref "U5") (pin "13") (pinfunction "GLB_13") (pintype "bidirectional"))
    )
    (net (code "27") (name "/GLC") (class "Default")
      (node (ref "Q6") (pin "4") (pinfunction "G_4") (pintype "passive"))
      (node (ref "U5") (pin "18") (pinfunction "GLC_18") (pintype "bidirectional"))
    )
    (net (code "28") (name "/I2C_ABS_SCL") (class "Default")
      (node (ref "ABS") (pin "2") (pinfunction "2_2") (pintype "passive"))
      (node (ref "R4") (pin "P$2") (pinfunction "P$2_P$2") (pintype "passive"))
      (node (ref "U1") (pin "46") (pinfunction "PB8-BOOT0_46") (pintype "bidirectional"))
    )
    (net (code "29") (name "/I2C_ABS_SDA") (class "Default")
      (node (ref "ABS") (pin "3") (pinfunction "3_3") (pintype "passive"))
      (node (ref "R3") (pin "P$2") (pinfunction "P$2_P$2") (pintype "passive"))
      (node (ref "U1") (pin "47") (pinfunction "PB9_47") (pintype "bidirectional"))
    )
    (net (code "30") (name "/LED1") (class "Default")
      (node (ref "D3") (pin "CATHODE") (pinfunction "CATHODE_CATHODE") (pintype "power_in"))
      (node (ref "U1") (pin "5") (pinfunction "PF0-OSC_IN_5") (pintype "bidirectional"))
    )
    (net (code "31") (name "/LED2") (class "Default")
      (node (ref "D2") (pin "CATHODE") (pinfunction "CATHODE_CATHODE") (pintype "power_in"))
      (node (ref "U1") (pin "6") (pinfunction "PF1-OSC_OUT_6") (pintype "bidirectional"))
    )
    (net (code "32") (name "/MOTOR1") (class "Default")
      (node (ref "MOT1") (pin "P$1") (pinfunction "P$1_P$1") (pintype "bidirectional"))
      (node (ref "U1") (pin "8") (pinfunction "PA0_8") (pintype "bidirectional"))
      (node (ref "U5") (pin "32") (pinfunction "INHA_32") (pintype "bidirectional"))
    )
    (net (code "33") (name "/MOTOR2") (class "Default")
      (node (ref "MOT2") (pin "P$1") (pinfunction "P$1_P$1") (pintype "bidirectional"))
      (node (ref "U1") (pin "9") (pinfunction "PA1_9") (pintype "bidirectional"))
      (node (ref "U5") (pin "34") (pinfunction "INHB_34") (pintype "bidirectional"))
    )
    (net (code "34") (name "/MOTOR3") (class "Default")
      (node (ref "MOT3") (pin "P$1") (pinfunction "P$1_P$1") (pintype "bidirectional"))
      (node (ref "U1") (pin "10") (pinfunction "PA2_10") (pintype "bidirectional"))
      (node (ref "U5") (pin "36") (pinfunction "INHC_36") (pintype "bidirectional"))
    )
    (net (code "35") (name "/MOTOR_ENABLE") (class "Default")
      (node (ref "U1") (pin "11") (pinfunction "PA3_11") (pintype "bidirectional"))
      (node (ref "U5") (pin "31") (pinfunction "ENABLE_31") (pintype "bidirectional"))
    )
    (net (code "36") (name "/MOTOR_FAULT") (class "Default")
      (node (ref "R14") (pin "P$2") (pinfunction "P$2_P$2") (pintype "passive"))
      (node (ref "U1") (pin "44") (pinfunction "PB6_44") (pintype "bidirectional"))
      (node (ref "U5") (pin "26") (pinfunction "FAULT_26") (pintype "bidirectional"))
    )
    (net (code "37") (name "/MOTOR_HIZ") (class "Default")
      (node (ref "U1") (pin "45") (pinfunction "PB7_45") (pintype "bidirectional"))
      (node (ref "U5") (pin "33") (pinfunction "INLA_33") (pintype "bidirectional"))
      (node (ref "U5") (pin "35") (pinfunction "INLB_35") (pintype "bidirectional"))
      (node (ref "U5") (pin "37") (pinfunction "INLC_37") (pintype "bidirectional"))
    )
    (net (code "38") (name "/NRST") (class "Default")
      (node (ref "C3") (pin "P$1") (pinfunction "P$1_P$1") (pintype "passive"))
      (node (ref "SWD") (pin "2") (pinfunction "2_2") (pintype "passive"))
      (node (ref "U1") (pin "7") (pinfunction "PG10-NRST_7") (pintype "bidirectional"))
    )
    (net (code "39") (name "/SECONDARY_ENC_CS") (class "Default")
      (node (ref "ENC") (pin "2") (pinfunction "2_2") (pintype "passive"))
      (node (ref "U1") (pin "2") (pinfunction "PC13_2") (pintype "bidirectional"))
    )
    (net (code "40") (name "/SHA") (class "Default")
      (node (ref "A") (pin "1") (pinfunction "P$1_1") (pintype "bidirectional"))
      (node (ref "DA") (pin "P$1") (pinfunction "P$1_P$1") (pintype "bidirectional"))
      (node (ref "Q1") (pin "1") (pinfunction "S_1") (pintype "passive"))
      (node (ref "Q1") (pin "2") (pinfunction "S_2") (pintype "passive"))
      (node (ref "Q1") (pin "3") (pinfunction "S_3") (pintype "passive"))
      (node (ref "Q2") (pin "5") (pinfunction "D_5") (pintype "passive"))
      (node (ref "Q2") (pin "6") (pinfunction "D_6") (pintype "passive"))
      (node (ref "Q2") (pin "7") (pinfunction "D_7") (pintype "passive"))
      (node (ref "Q2") (pin "8") (pinfunction "D_8") (pintype "passive"))
      (node (ref "Q2") (pin "PAD") (pinfunction "D_PAD") (pintype "passive"))
      (node (ref "U5") (pin "7") (pinfunction "SHA_7") (pintype "bidirectional"))
    )
    (net (code "41") (name "/SHB") (class "Default")
      (node (ref "B") (pin "1") (pinfunction "P$1_1") (pintype "bidirectional"))
      (node (ref "DB") (pin "P$1") (pinfunction "P$1_P$1") (pintype "bidirectional"))
      (node (ref "Q3") (pin "1") (pinfunction "S_1") (pintype "passive"))
      (node (ref "Q3") (pin "2") (pinfunction "S_2") (pintype "passive"))
      (node (ref "Q3") (pin "3") (pinfunction "S_3") (pintype "passive"))
      (node (ref "Q4") (pin "5") (pinfunction "D_5") (pintype "passive"))
      (node (ref "Q4") (pin "6") (pinfunction "D_6") (pintype "passive"))
      (node (ref "Q4") (pin "7") (pinfunction "D_7") (pintype "passive"))
      (node (ref "Q4") (pin "8") (pinfunction "D_8") (pintype "passive"))
      (node (ref "Q4") (pin "PAD") (pinfunction "D_PAD") (pintype "passive"))
      (node (ref "U5") (pin "14") (pinfunction "SHB_14") (pintype "bidirectional"))
    )
    (net (code "42") (name "/SHC") (class "Default")
      (node (ref "C") (pin "1") (pinfunction "P$1_1") (pintype "bidirectional"))
      (node (ref "DC") (pin "P$1") (pinfunction "P$1_P$1") (pintype "bidirectional"))
      (node (ref "Q5") (pin "1") (pinfunction "S_1") (pintype "passive"))
      (node (ref "Q5") (pin "2") (pinfunction "S_2") (pintype "passive"))
      (node (ref "Q5") (pin "3") (pinfunction "S_3") (pintype "passive"))
      (node (ref "Q6") (pin "5") (pinfunction "D_5") (pintype "passive"))
      (node (ref "Q6") (pin "6") (pinfunction "D_6") (pintype "passive"))
      (node (ref "Q6") (pin "7") (pinfunction "D_7") (pintype "passive"))
      (node (ref "Q6") (pin "8") (pinfunction "D_8") (pintype "passive"))
      (node (ref "Q6") (pin "PAD") (pinfunction "D_PAD") (pintype "passive"))
      (node (ref "U5") (pin "17") (pinfunction "SHC_17") (pintype "bidirectional"))
    )
    (net (code "43") (name "/SNA") (class "Default")
      (node (ref "SH1") (pin "1") (pinfunction "P$1_1") (pintype "bidirectional"))
      (node (ref "U5") (pin "10") (pinfunction "SNA_10") (pintype "bidirectional"))
    )
    (net (code "44") (name "/SNB") (class "Default")
      (node (ref "SH2") (pin "1") (pinfunction "P$1_1") (pintype "bidirectional"))
      (node (ref "U5") (pin "11") (pinfunction "SNB_11") (pintype "bidirectional"))
    )
    (net (code "45") (name "/SNC") (class "Default")
      (node (ref "SH3") (pin "1") (pinfunction "P$1_1") (pintype "bidirectional"))
      (node (ref "U5") (pin "20") (pinfunction "SNC_20") (pintype "bidirectional"))
    )
    (net (code "46") (name "/SPA") (class "Default")
      (node (ref "Q2") (pin "1") (pinfunction "S_1") (pintype "passive"))
      (node (ref "Q2") (pin "2") (pinfunction "S_2") (pintype "passive"))
      (node (ref "Q2") (pin "3") (pinfunction "S_3") (pintype "passive"))
      (node (ref "RA") (pin "2") (pinfunction "2_2") (pintype "passive"))
      (node (ref "U5") (pin "9") (pinfunction "SPA_9") (pintype "bidirectional"))
    )
    (net (code "47") (name "/SPB") (class "Default")
      (node (ref "Q4") (pin "1") (pinfunction "S_1") (pintype "passive"))
      (node (ref "Q4") (pin "2") (pinfunction "S_2") (pintype "passive"))
      (node (ref "Q4") (pin "3") (pinfunction "S_3") (pintype "passive"))
      (node (ref "RB") (pin "2") (pinfunction "2_2") (pintype "passive"))
      (node (ref "U5") (pin "12") (pinfunction "SPB_12") (pintype "bidirectional"))
    )
    (net (code "48") (name "/SPC") (class "Default")
      (node (ref "Q6") (pin "1") (pinfunction "S_1") (pintype "passive"))
      (node (ref "Q6") (pin "2") (pinfunction "S_2") (pintype "passive"))
      (node (ref "Q6") (pin "3") (pinfunction "S_3") (pintype "passive"))
      (node (ref "RC") (pin "2") (pinfunction "2_2") (pintype "passive"))
      (node (ref "U5") (pin "19") (pinfunction "SPC_19") (pintype "bidirectional"))
    )
    (net (code "49") (name "/SWCLK") (class "Default")
      (node (ref "SWD") (pin "5") (pinfunction "5_5") (pintype "passive"))
      (node (ref "U1") (pin "37") (pinfunction "PA14_37") (pintype "bidirectional"))
    )
    (net (code "50") (name "/SWDIO") (class "Default")
      (node (ref "SWD") (pin "3") (pinfunction "3_3") (pintype "passive"))
      (node (ref "U1") (pin "36") (pinfunction "PA13_36") (pintype "bidirectional"))
    )
    (net (code "51") (name "/VBAT_SENSE") (class "Default")
      (node (ref "R5") (pin "P$1") (pinfunction "P$1_P$1") (pintype "passive"))
      (node (ref "R6") (pin "P$2") (pinfunction "P$2_P$2") (pintype "passive"))
      (node (ref "U1") (pin "25") (pinfunction "PB12_25") (pintype "bidirectional"))
    )
    (net (code "52") (name "/VSW") (class "Default")
      (node (ref "L1") (pin "2") (pinfunction "2_2") (pintype "passive"))
      (node (ref "U4") (pin "8") (pinfunction "LX_8") (pintype "passive"))
    )
    (net (code "53") (name "/VTEMP_FET") (class "Default")
      (node (ref "C13") (pin "P$1") (pinfunction "P$1_P$1") (pintype "passive"))
      (node (ref "R8") (pin "P$2") (pinfunction "P$2_P$2") (pintype "passive"))
      (node (ref "R9") (pin "P$1") (pinfunction "P$1_P$1") (pintype "passive"))
      (node (ref "U1") (pin "31") (pinfunction "PA9_31") (pintype "bidirectional"))
    )
    (net (code "54") (name "/VTEMP_MOT") (class "Default")
      (node (ref "R7") (pin "P$1") (pinfunction "P$1_P$1") (pintype "passive"))
      (node (ref "TEMP2") (pin "P$1") (pinfunction "P$1_P$1") (pintype "bidirectional"))
      (node (ref "U1") (pin "30") (pinfunction "PA8_30") (pintype "bidirectional"))
    )
    (net (code "55") (name "GND") (class "Default")
      (node (ref "ABS") (pin "4") (pinfunction "4_4") (pintype "passive"))
      (node (ref "C1") (pin "P$2") (pinfunction "P$2_P$2") (pintype "passive"))
      (node (ref "C10") (pin "P$2") (pinfunction "P$2_P$2") (pintype "passive"))
      (node (ref "C11") (pin "P$2") (pinfunction "P$2_P$2") (pintype "passive"))
      (node (ref "C12") (pin "P$2") (pinfunction "P$2_P$2") (pintype "passive"))
      (node (ref "C13") (pin "P$2") (pinfunction "P$2_P$2") (pintype "passive"))
      (node (ref "C17") (pin "P$1") (pinfunction "P$1_P$1") (pintype "passive"))
      (node (ref "C18") (pin "P$1") (pinfunction "P$1_P$1") (pintype "passive"))
      (node (ref "C2") (pin "P$2") (pinfunction "P$2_P$2") (pintype "passive"))
      (node (ref "C20") (pin "P$2") (pinfunction "P$2_P$2") (pintype "passive"))
      (node (ref "C21") (pin "P$2") (pinfunction "P$2_P$2") (pintype "passive"))
      (node (ref "C3") (pin "P$2") (pinfunction "P$2_P$2") (pintype "passive"))
      (node (ref "C4") (pin "P$2") (pinfunction "P$2_P$2") (pintype "passive"))
      (node (ref "C5") (pin "P$2") (pinfunction "P$2_P$2") (pintype "passive"))
      (node (ref "C6") (pin "P$2") (pinfunction "P$2_P$2") (pintype "passive"))
      (node (ref "C7") (pin "P$1") (pinfunction "P$1_P$1") (pintype "passive"))
      (node (ref "C8") (pin "P$2") (pinfunction "P$2_P$2") (pintype "passive"))
      (node (ref "C9") (pin "P$2") (pinfunction "P$2_P$2") (pintype "passive"))
      (node (ref "CAN1") (pin "3") (pinfunction "3_3") (pintype "passive"))
      (node (ref "CAN2") (pin "3") (pinfunction "3_3") (pintype "passive"))
      (node (ref "DG1") (pin "P$1") (pinfunction "P$1_P$1") (pintype "bidirectional"))
      (node (ref "DG2") (pin "P$1") (pinfunction "P$1_P$1") (pintype "bidirectional"))
      (node (ref "ENC") (pin "3") (pinfunction "3_3") (pintype "passive"))
      (node (ref "R6") (pin "P$1") (pinfunction "P$1_P$1") (pintype "passive"))
      (node (ref "R7") (pin "P$2") (pinfunction "P$2_P$2") (pintype "passive"))
      (node (ref "R9") (pin "P$2") (pinfunction "P$2_P$2") (pintype "passive"))
      (node (ref "SH4") (pin "2") (pinfunction "P$2_2") (pintype "bidirectional"))
      (node (ref "SWD") (pin "4") (pinfunction "4_4") (pintype "passive"))
      (node (ref "U1") (pin "29") (pinfunction "PC6_29") (pintype "bidirectional"))
      (node (ref "U1") (pin "38") (pinfunction "PA15_38") (pintype "bidirectional"))
      (node (ref "U1") (pin "49") (pinfunction "THERMALPAD_49") (pintype "bidirectional"))
      (node (ref "U2") (pin "2") (pinfunction "GND_2") (pintype "power_in"))
      (node (ref "U2") (pin "5") (pinfunction "SHDN_5") (pintype "input"))
      (node (ref "U2") (pin "8") (pinfunction "STB_8") (pintype "input"))
      (node (ref "U3") (pin "13") (pinfunction "GND_13") (pintype "bidirectional"))
      (node (ref "U3") (pin "5") (pinfunction "TEST_5") (pintype "bidirectional"))
      (node (ref "U4") (pin "7") (pinfunction "GND_7") (pintype "power_in"))
      (node (ref "U5") (pin "39") (pinfunction "GND_39") (pintype "bidirectional"))
    )
    (net (code "56") (name "Net-(C55-PadP$1)") (class "Default")
      (node (ref "C55") (pin "P$1") (pinfunction "P$1_P$1") (pintype "passive"))
      (node (ref "M3") (pin "P$1") (pinfunction "P$1_P$1") (pintype "bidirectional"))
      (node (ref "R10") (pin "P$1") (pinfunction "P$1_P$1") (pintype "passive"))
    )
    (net (code "57") (name "Net-(D2-PadANODE)") (class "Default")
      (node (ref "D2") (pin "ANODE") (pinfunction "ANODE_ANODE") (pintype "power_in"))
      (node (ref "R2") (pin "P$2") (pinfunction "P$2_P$2") (pintype "passive"))
    )
    (net (code "58") (name "Net-(D3-PadANODE)") (class "Default")
      (node (ref "D3") (pin "ANODE") (pinfunction "ANODE_ANODE") (pintype "power_in"))
      (node (ref "R1") (pin "P$2") (pinfunction "P$2_P$2") (pintype "passive"))
    )
    (net (code "59") (name "Net-(U2-CANH)") (class "Default")
      (node (ref "CAN1") (pin "1") (pinfunction "1_1") (pintype "passive"))
      (node (ref "CAN2") (pin "1") (pinfunction "1_1") (pintype "passive"))
      (node (ref "U2") (pin "7") (pinfunction "CANH_7") (pintype "bidirectional"))
    )
    (net (code "60") (name "Net-(U2-CANL)") (class "Default")
      (node (ref "CAN1") (pin "2") (pinfunction "2_2") (pintype "passive"))
      (node (ref "CAN2") (pin "2") (pinfunction "2_2") (pintype "passive"))
      (node (ref "U2") (pin "6") (pinfunction "CANL_6") (pintype "bidirectional"))
    )
    (net (code "61") (name "Net-(U4-VCC)") (class "Default")
      (node (ref "C20") (pin "P$1") (pinfunction "P$1_P$1") (pintype "passive"))
      (node (ref "U4") (pin "3") (pinfunction "VCC_3") (pintype "power_in"))
    )
    (net (code "62") (name "Net-(U5-CPH)") (class "Default")
      (node (ref "C16") (pin "P$1") (pinfunction "P$1_P$1") (pintype "passive"))
      (node (ref "U5") (pin "2") (pinfunction "CPH_2") (pintype "bidirectional"))
    )
    (net (code "63") (name "Net-(U5-CPL)") (class "Default")
      (node (ref "C16") (pin "P$2") (pinfunction "P$2_P$2") (pintype "passive"))
      (node (ref "U5") (pin "1") (pinfunction "CPL_1") (pintype "bidirectional"))
    )
    (net (code "64") (name "Net-(U5-DVDD)") (class "Default")
      (node (ref "C17") (pin "P$2") (pinfunction "P$2_P$2") (pintype "passive"))
      (node (ref "U5") (pin "38") (pinfunction "DVDD_38") (pintype "bidirectional"))
    )
    (net (code "65") (name "Net-(U5-VCP)") (class "Default")
      (node (ref "C15") (pin "P$2") (pinfunction "P$2_P$2") (pintype "passive"))
      (node (ref "U5") (pin "5") (pinfunction "VCP_5") (pintype "bidirectional"))
    )
    (net (code "66") (name "Net-(U5-VGLS)") (class "Default")
      (node (ref "C38") (pin "P$2") (pinfunction "P$2_P$2") (pintype "passive"))
      (node (ref "U5") (pin "40") (pinfunction "VGLS_40") (pintype "bidirectional"))
    )
    (net (code "67") (name "V+") (class "Default")
      (node (ref "C14") (pin "P$1") (pinfunction "P$1_P$1") (pintype "passive"))
      (node (ref "C15") (pin "P$1") (pinfunction "P$1_P$1") (pintype "passive"))
      (node (ref "C19") (pin "P$1") (pinfunction "P$1_P$1") (pintype "passive"))
      (node (ref "C22") (pin "P$1") (pinfunction "P$1_P$1") (pintype "passive"))
      (node (ref "C23") (pin "P$1") (pinfunction "P$1_P$1") (pintype "passive"))
      (node (ref "C24") (pin "P$1") (pinfunction "P$1_P$1") (pintype "passive"))
      (node (ref "C25") (pin "P$1") (pinfunction "P$1_P$1") (pintype "passive"))
      (node (ref "C26") (pin "P$1") (pinfunction "P$1_P$1") (pintype "passive"))
      (node (ref "C27") (pin "P$1") (pinfunction "P$1_P$1") (pintype "passive"))
      (node (ref "C28") (pin "P$1") (pinfunction "P$1_P$1") (pintype "passive"))
      (node (ref "C29") (pin "P$1") (pinfunction "P$1_P$1") (pintype "passive"))
      (node (ref "C30") (pin "P$1") (pinfunction "P$1_P$1") (pintype "passive"))
      (node (ref "C31") (pin "P$1") (pinfunction "P$1_P$1") (pintype "passive"))
      (node (ref "C32") (pin "P$1") (pinfunction "P$1_P$1") (pintype "passive"))
      (node (ref "C33") (pin "P$1") (pinfunction "P$1_P$1") (pintype "passive"))
      (node (ref "C34") (pin "P$1") (pinfunction "P$1_P$1") (pintype "passive"))
      (node (ref "C35") (pin "P$1") (pinfunction "P$1_P$1") (pintype "passive"))
      (node (ref "C36") (pin "P$1") (pinfunction "P$1_P$1") (pintype "passive"))
      (node (ref "C37") (pin "P$1") (pinfunction "P$1_P$1") (pintype "passive"))
      (node (ref "C39") (pin "P$1") (pinfunction "P$1_P$1") (pintype "passive"))
      (node (ref "C40") (pin "P$1") (pinfunction "P$1_P$1") (pintype "passive"))
      (node (ref "C41") (pin "P$1") (pinfunction "P$1_P$1") (pintype "passive"))
      (node (ref "C42") (pin "P$1") (pinfunction "P$1_P$1") (pintype "passive"))
      (node (ref "C43") (pin "P$1") (pinfunction "P$1_P$1") (pintype "passive"))
      (node (ref "C44") (pin "P$1") (pinfunction "P$1_P$1") (pintype "passive"))
      (node (ref "C45") (pin "P$1") (pinfunction "P$1_P$1") (pintype "passive"))
      (node (ref "C46") (pin "P$1") (pinfunction "P$1_P$1") (pintype "passive"))
      (node (ref "C47") (pin "P$1") (pinfunction "P$1_P$1") (pintype "passive"))
      (node (ref "C48") (pin "P$1") (pinfunction "P$1_P$1") (pintype "passive"))
      (node (ref "C49") (pin "P$1") (pinfunction "P$1_P$1") (pintype "passive"))
      (node (ref "C50") (pin "P$1") (pinfunction "P$1_P$1") (pintype "passive"))
      (node (ref "C51") (pin "P$1") (pinfunction "P$1_P$1") (pintype "passive"))
      (node (ref "C52") (pin "P$1") (pinfunction "P$1_P$1") (pintype "passive"))
      (node (ref "C53") (pin "P$1") (pinfunction "P$1_P$1") (pintype "passive"))
      (node (ref "C54") (pin "P$1") (pinfunction "P$1_P$1") (pintype "passive"))
      (node (ref "J1") (pin "1") (pinfunction "1_1") (pintype "passive"))
      (node (ref "J2") (pin "1") (pinfunction "1_1") (pintype "passive"))
      (node (ref "Q1") (pin "5") (pinfunction "D_5") (pintype "passive"))
      (node (ref "Q1") (pin "6") (pinfunction "D_6") (pintype "passive"))
      (node (ref "Q1") (pin "7") (pinfunction "D_7") (pintype "passive"))
      (node (ref "Q1") (pin "8") (pinfunction "D_8") (pintype "passive"))
      (node (ref "Q1") (pin "PAD") (pinfunction "D_PAD") (pintype "passive"))
      (node (ref "Q3") (pin "5") (pinfunction "D_5") (pintype "passive"))
      (node (ref "Q3") (pin "6") (pinfunction "D_6") (pintype "passive"))
      (node (ref "Q3") (pin "7") (pinfunction "D_7") (pintype "passive"))
      (node (ref "Q3") (pin "8") (pinfunction "D_8") (pintype "passive"))
      (node (ref "Q3") (pin "PAD") (pinfunction "D_PAD") (pintype "passive"))
      (node (ref "Q5") (pin "5") (pinfunction "D_5") (pintype "passive"))
      (node (ref "Q5") (pin "6") (pinfunction "D_6") (pintype "passive"))
      (node (ref "Q5") (pin "7") (pinfunction "D_7") (pintype "passive"))
      (node (ref "Q5") (pin "8") (pinfunction "D_8") (pintype "passive"))
      (node (ref "Q5") (pin "PAD") (pinfunction "D_PAD") (pintype "passive"))
      (node (ref "R5") (pin "P$2") (pinfunction "P$2_P$2") (pintype "passive"))
      (node (ref "U4") (pin "1") (pinfunction "VIN_1") (pintype "input"))
      (node (ref "U4") (pin "2") (pinfunction "EN/UVLO_2") (pintype "input"))
      (node (ref "U5") (pin "3") (pinfunction "VM_3") (pintype "bidirectional"))
      (node (ref "U5") (pin "4") (pinfunction "VDRAIN_4") (pintype "bidirectional"))
    )
    (net (code "68") (name "V-") (class "Default")
      (node (ref "C14") (pin "P$2") (pinfunction "P$2_P$2") (pintype "passive"))
      (node (ref "C19") (pin "P$2") (pinfunction "P$2_P$2") (pintype "passive"))
      (node (ref "C22") (pin "P$2") (pinfunction "P$2_P$2") (pintype "passive"))
      (node (ref "C23") (pin "P$2") (pinfunction "P$2_P$2") (pintype "passive"))
      (node (ref "C24") (pin "P$2") (pinfunction "P$2_P$2") (pintype "passive"))
      (node (ref "C25") (pin "P$2") (pinfunction "P$2_P$2") (pintype "passive"))
      (node (ref "C26") (pin "P$2") (pinfunction "P$2_P$2") (pintype "passive"))
      (node (ref "C27") (pin "P$2") (pinfunction "P$2_P$2") (pintype "passive"))
      (node (ref "C28") (pin "P$2") (pinfunction "P$2_P$2") (pintype "passive"))
      (node (ref "C29") (pin "P$2") (pinfunction "P$2_P$2") (pintype "passive"))
      (node (ref "C30") (pin "P$2") (pinfunction "P$2_P$2") (pintype "passive"))
      (node (ref "C31") (pin "P$2") (pinfunction "P$2_P$2") (pintype "passive"))
      (node (ref "C32") (pin "P$2") (pinfunction "P$2_P$2") (pintype "passive"))
      (node (ref "C33") (pin "P$2") (pinfunction "P$2_P$2") (pintype "passive"))
      (node (ref "C34") (pin "P$2") (pinfunction "P$2_P$2") (pintype "passive"))
      (node (ref "C35") (pin "P$2") (pinfunction "P$2_P$2") (pintype "passive"))
      (node (ref "C36") (pin "P$2") (pinfunction "P$2_P$2") (pintype "passive"))
      (node (ref "C37") (pin "P$2") (pinfunction "P$2_P$2") (pintype "passive"))
      (node (ref "C38") (pin "P$1") (pinfunction "P$1_P$1") (pintype "passive"))
      (node (ref "C39") (pin "P$2") (pinfunction "P$2_P$2") (pintype "passive"))
      (node (ref "C40") (pin "P$2") (pinfunction "P$2_P$2") (pintype "passive"))
      (node (ref "C41") (pin "P$2") (pinfunction "P$2_P$2") (pintype "passive"))
      (node (ref "C42") (pin "P$2") (pinfunction "P$2_P$2") (pintype "passive"))
      (node (ref "C43") (pin "P$2") (pinfunction "P$2_P$2") (pintype "passive"))
      (node (ref "C44") (pin "P$2") (pinfunction "P$2_P$2") (pintype "passive"))
      (node (ref "C45") (pin "P$2") (pinfunction "P$2_P$2") (pintype "passive"))
      (node (ref "C46") (pin "P$2") (pinfunction "P$2_P$2") (pintype "passive"))
      (node (ref "C47") (pin "P$2") (pinfunction "P$2_P$2") (pintype "passive"))
      (node (ref "C48") (pin "P$2") (pinfunction "P$2_P$2") (pintype "passive"))
      (node (ref "C49") (pin "P$2") (pinfunction "P$2_P$2") (pintype "passive"))
      (node (ref "C50") (pin "P$2") (pinfunction "P$2_P$2") (pintype "passive"))
      (node (ref "C51") (pin "P$2") (pinfunction "P$2_P$2") (pintype "passive"))
      (node (ref "C52") (pin "P$2") (pinfunction "P$2_P$2") (pintype "passive"))
      (node (ref "C53") (pin "P$2") (pinfunction "P$2_P$2") (pintype "passive"))
      (node (ref "C54") (pin "P$2") (pinfunction "P$2_P$2") (pintype "passive"))
      (node (ref "C55") (pin "P$2") (pinfunction "P$2_P$2") (pintype "passive"))
      (node (ref "J1") (pin "2") (pinfunction "2_2") (pintype "passive"))
      (node (ref "J2") (pin "2") (pinfunction "2_2") (pintype "passive"))
      (node (ref "R10") (pin "P$2") (pinfunction "P$2_P$2") (pintype "passive"))
      (node (ref "RA") (pin "1") (pinfunction "1_1") (pintype "passive"))
      (node (ref "RB") (pin "1") (pinfunction "1_1") (pintype "passive"))
      (node (ref "RC") (pin "1") (pinfunction "1_1") (pintype "passive"))
      (node (ref "SH1") (pin "2") (pinfunction "P$2_2") (pintype "bidirectional"))
      (node (ref "SH2") (pin "2") (pinfunction "P$2_2") (pintype "bidirectional"))
      (node (ref "SH3") (pin "2") (pinfunction "P$2_2") (pintype "bidirectional"))
      (node (ref "SH4") (pin "1") (pinfunction "P$1_1") (pintype "bidirectional"))
      (node (ref "U5") (pin "25") (pinfunction "AGND_25") (pintype "bidirectional"))
      (node (ref "U5") (pin "P1") (pinfunction "PAD_P1") (pintype "bidirectional"))
      (node (ref "U5") (pin "P12") (pinfunction "PAD_P12") (pintype "bidirectional"))
      (node (ref "U5") (pin "P13") (pinfunction "PAD_P13") (pintype "bidirectional"))
      (node (ref "U5") (pin "P14") (pinfunction "PAD_P14") (pintype "bidirectional"))
      (node (ref "U5") (pin "P17") (pinfunction "PAD_P17") (pintype "bidirectional"))
      (node (ref "U5") (pin "P18") (pinfunction "PAD_P18") (pintype "bidirectional"))
      (node (ref "U5") (pin "P19") (pinfunction "PAD_P19") (pintype "bidirectional"))
      (node (ref "U5") (pin "P2") (pinfunction "PAD_P2") (pintype "bidirectional"))
      (node (ref "U5") (pin "P3") (pinfunction "PAD_P3") (pintype "bidirectional"))
      (node (ref "U5") (pin "P7") (pinfunction "PAD_P7") (pintype "bidirectional"))
      (node (ref "U5") (pin "P8") (pinfunction "PAD_P8") (pintype "bidirectional"))
      (node (ref "U5") (pin "P9") (pinfunction "PAD_P9") (pintype "bidirectional"))
      (node (ref "U5") (pin "PAD") (pinfunction "PAD_PAD") (pintype "bidirectional"))
    )
    (net (code "69") (name "unconnected-(M1-PadP$1)") (class "Default")
      (node (ref "M1") (pin "P$1") (pinfunction "P$1_P$1") (pintype "bidirectional"))
    )
    (net (code "70") (name "unconnected-(M2-PadP$1)") (class "Default")
      (node (ref "M2") (pin "P$1") (pinfunction "P$1_P$1") (pintype "bidirectional"))
    )
    (net (code "71") (name "unconnected-(M4-PadP$1)") (class "Default")
      (node (ref "M4") (pin "P$1") (pinfunction "P$1_P$1") (pintype "bidirectional"))
    )
    (net (code "72") (name "unconnected-(SWD-Pad1)") (class "Default")
      (node (ref "SWD") (pin "1") (pinfunction "1_1") (pintype "passive"))
    )
    (net (code "73") (name "unconnected-(U1-PA10-Pad32)") (class "Default")
      (node (ref "U1") (pin "32") (pinfunction "PA10_32") (pintype "bidirectional"))
    )
    (net (code "74") (name "unconnected-(U1-PB3-Pad41)") (class "Default")
      (node (ref "U1") (pin "41") (pinfunction "PB3_41") (pintype "bidirectional"))
    )
    (net (code "75") (name "unconnected-(U1-PB10-Pad22)") (class "Default")
      (node (ref "U1") (pin "22") (pinfunction "PB10_22") (pintype "bidirectional"))
    )
    (net (code "76") (name "unconnected-(U3-I-Pad14)") (class "Default")
      (node (ref "U3") (pin "14") (pinfunction "I_14") (pintype "bidirectional"))
    )
    (net (code "77") (name "unconnected-(U3-PWM-Pad8)") (class "Default")
      (node (ref "U3") (pin "8") (pinfunction "PWM_8") (pintype "bidirectional"))
    )
    (net (code "78") (name "unconnected-(U3-VDD5V-Pad11)") (class "Default")
      (node (ref "U3") (pin "11") (pinfunction "VDD5V_11") (pintype "bidirectional"))
    )
    (net (code "79") (name "unconnected-(U4-MODE-Pad5)") (class "Default")
      (node (ref "U4") (pin "5") (pinfunction "MODE_5") (pintype "input"))
    )
    (net (code "80") (name "unconnected-(U4-~{RESET}-Pad6)") (class "Default")
      (node (ref "U4") (pin "6") (pinfunction "~{RESET}_6") (pintype "output"))
    )
  )
)
